# ESC.net
KiCad netlist of a schematic drawn in Altium Designer
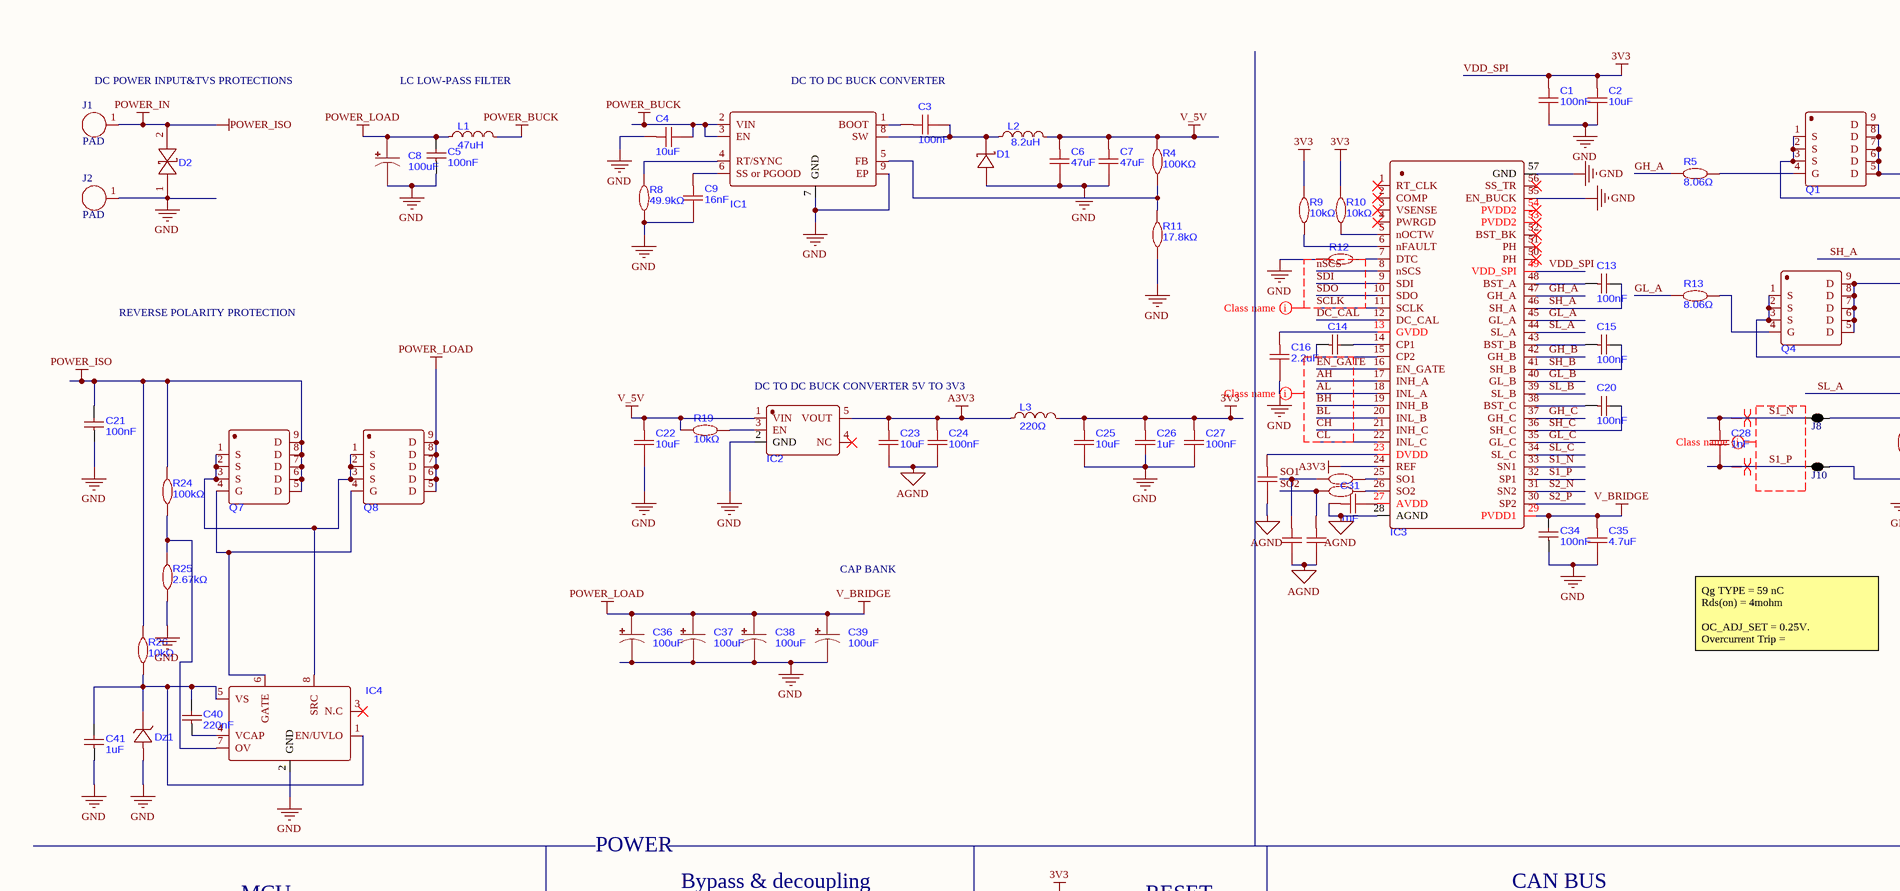
[diagram p0: ESC.SchDoc, top left]
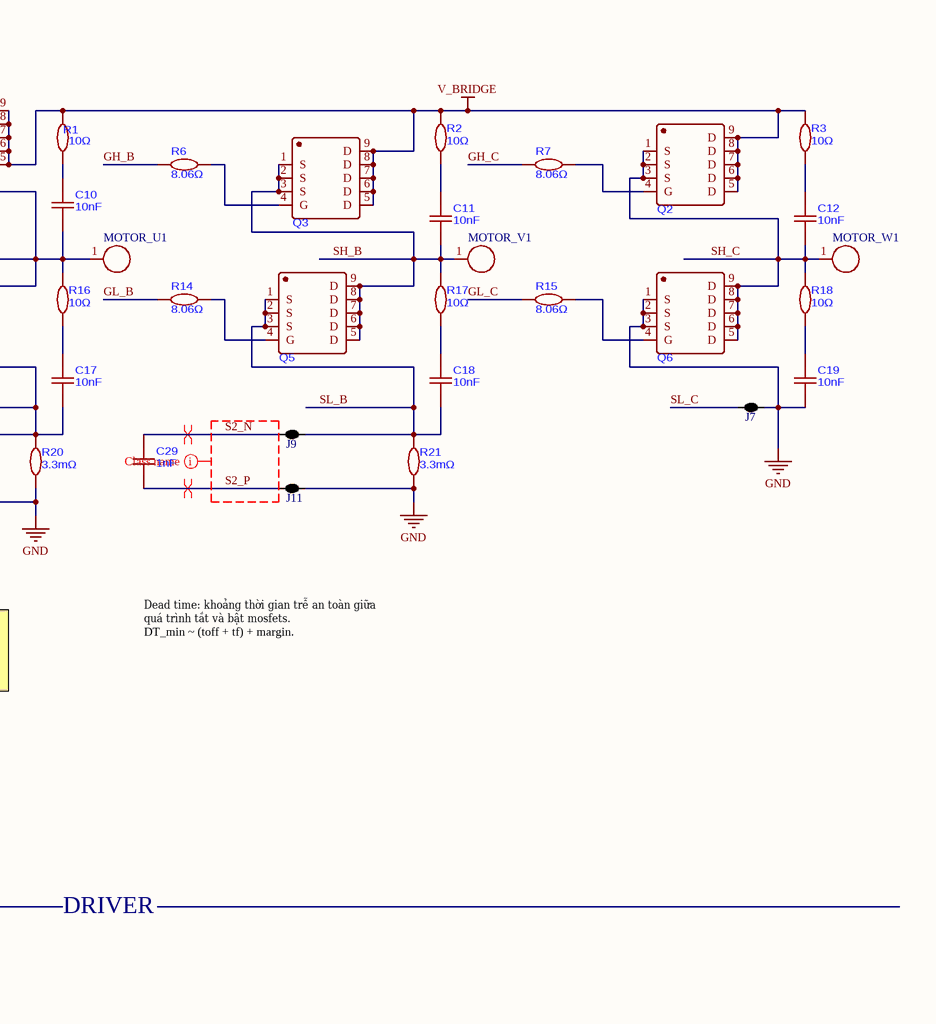
[diagram p1: ESC.SchDoc, top right]
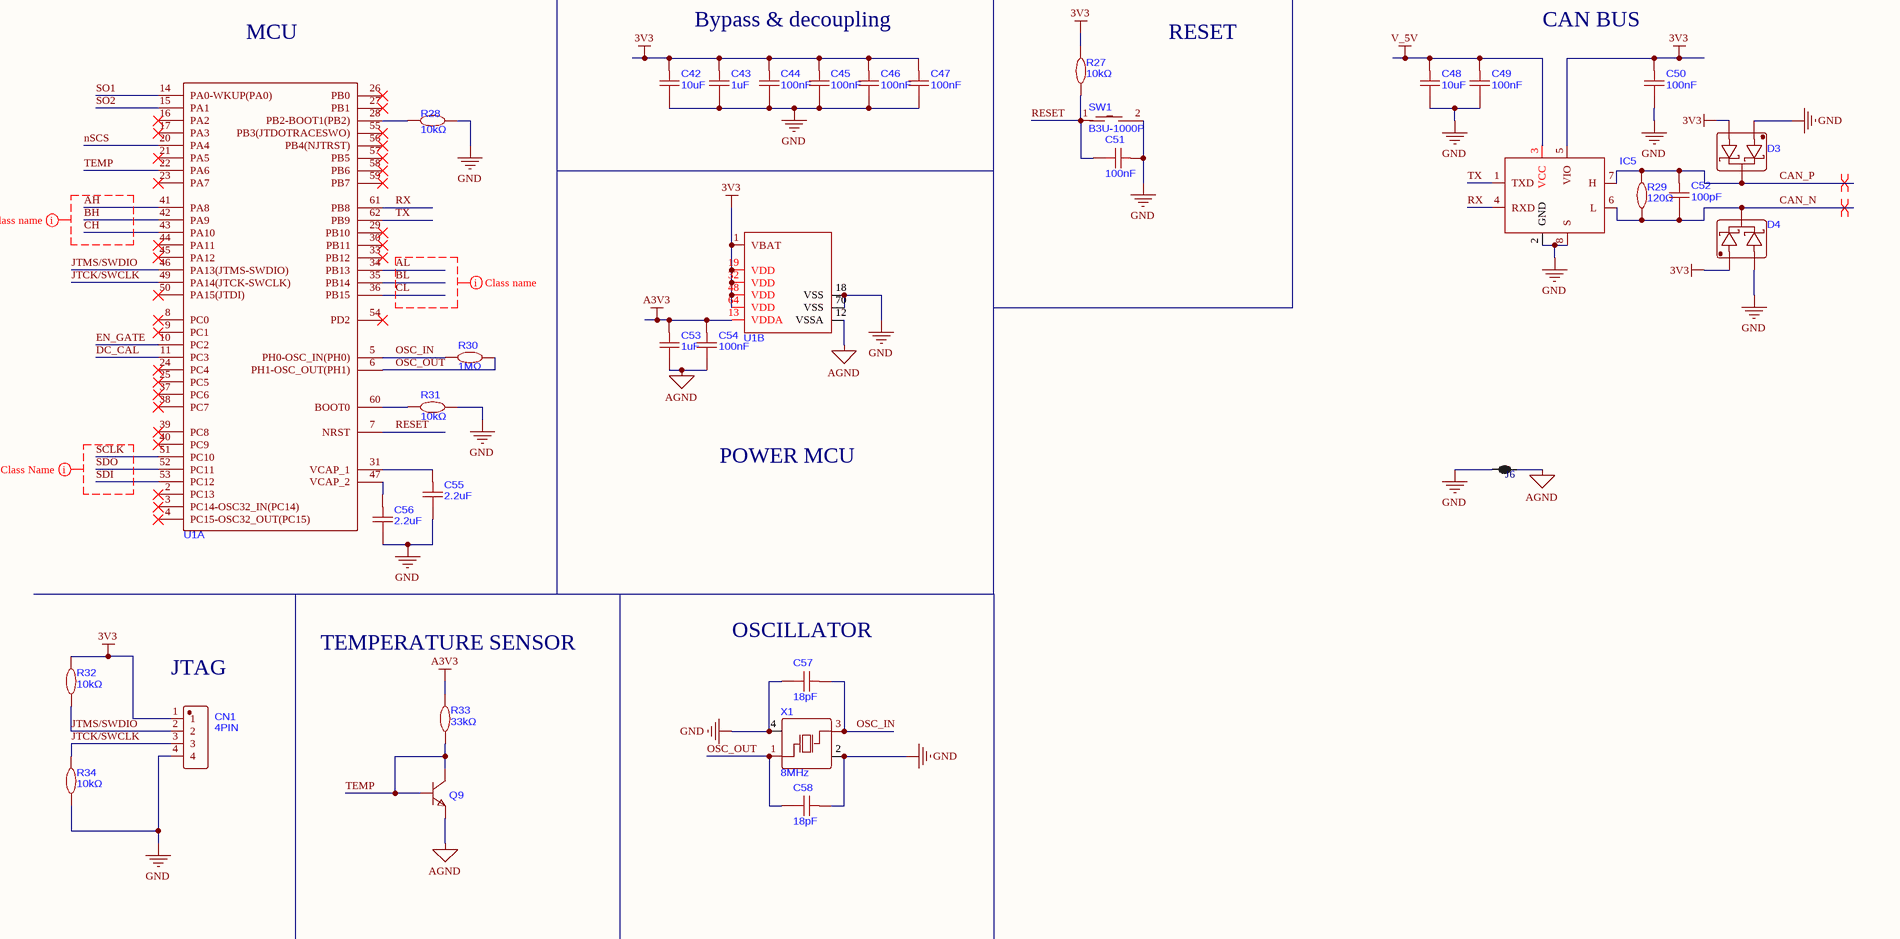
[diagram p2: ESC.SchDoc, bottom left]
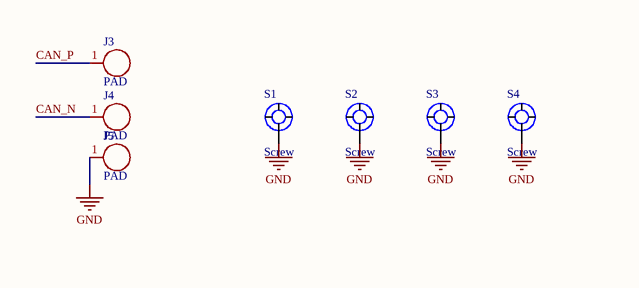
[diagram p3: ESC.SchDoc, bottom right]

(export (version "E")
  (design (tool "Eeschema 10.0.6"))
  (components
    (comp (ref "C1")
      (value "100nF")
      (footprint "C0603")
      (description "100nF ±10% 50V Ceramic Capacitor X7R 0603")
      (libsource (lib "ESC") (part "CC0603KRX7R9BB104"))
    )
    (comp (ref "C2")
      (value "10uF")
      (footprint "C0603")
      (description "10uF ±10% 10V Ceramic Capacitor X5R 0603")
      (libsource (lib "ESC") (part "CL10A106KP8NNNC"))
    )
    (comp (ref "C3")
      (value "100nF")
      (footprint "C0603")
      (description "100nF ±10% 50V Ceramic Capacitor X7R 0603")
      (libsource (lib "ESC") (part "CC0603KRX7R9BB104"))
    )
    (comp (ref "C4")
      (value "10uF")
      (footprint "C1206")
      (description "10uF X6S ±10% 100V 1206 Ceramic Capacitors RoHS")
      (libsource (lib "ESC") (part "C3216X6S2A106KT0A0E"))
    )
    (comp (ref "C5")
      (value "100nF")
      (footprint "C0805")
      (description "100nF ±10% 100V Ceramic Capacitor X7R 0805")
      (libsource (lib "ESC") (part "CL21B104KCFNNNE"))
    )
    (comp (ref "C6")
      (value "47uF")
      (footprint "C0603")
      (description "47uF ±20% 10V Ceramic Capacitor X5R 0805")
      (libsource (lib "ESC") (part "GRM21BR61A476ME15L_1"))
    )
    (comp (ref "C7")
      (value "47uF")
      (footprint "C0603")
      (description "47uF ±20% 10V Ceramic Capacitor X5R 0805")
      (libsource (lib "ESC") (part "GRM21BR61A476ME15L_1"))
    )
    (comp (ref "C8")
      (value "100uF")
      (footprint "CAP-SMD_BD10.0-L10.3-W10.3-FD")
      (description "100uF ±20% 100V Aluminum Electrolytic Capacitors")
      (libsource (lib "ESC") (part "EFVH100ADA101M10C0"))
    )
    (comp (ref "C9")
      (value "16nF")
      (footprint "C1206")
      (description "16nF ±5% 50V Ceramic Capacitor C0G 1206")
      (libsource (lib "ESC") (part "GRM3195C1H163JA01D"))
    )
    (comp (ref "C10")
      (value "10nF")
      (footprint "C0805")
      (description "10nF ±10% 100V Ceramic Capacitor X7R 0805")
      (libsource (lib "ESC") (part "CC0805KRX7R0BB103"))
    )
    (comp (ref "C11")
      (value "10nF")
      (footprint "C0805")
      (description "10nF ±10% 100V Ceramic Capacitor X7R 0805")
      (libsource (lib "ESC") (part "CC0805KRX7R0BB103"))
    )
    (comp (ref "C12")
      (value "10nF")
      (footprint "C0805")
      (description "10nF ±10% 100V Ceramic Capacitor X7R 0805")
      (libsource (lib "ESC") (part "CC0805KRX7R0BB103"))
    )
    (comp (ref "C13")
      (value "100nF")
      (footprint "C0805")
      (description "100nF ±10% 100V Ceramic Capacitor X7R 0805")
      (libsource (lib "ESC") (part "CL21B104KCFNNNE"))
    )
    (comp (ref "C14")
      (value "220nF")
      (footprint "C0805")
      (description "220nF ±10% 100V Ceramic Capacitor X7R 0805")
      (libsource (lib "ESC") (part "CC0805KKX7R0BB224"))
    )
    (comp (ref "C15")
      (value "100nF")
      (footprint "C0805")
      (description "100nF ±10% 100V Ceramic Capacitor X7R 0805")
      (libsource (lib "ESC") (part "CL21B104KCFNNNE"))
    )
    (comp (ref "C16")
      (value "2.2uF")
      (footprint "C0603")
      (description "2.2uF X5R ±10% 25V 0603 Ceramic Capacitors RoHS")
      (libsource (lib "ESC") (part "CC0603X5R25V225KN"))
    )
    (comp (ref "C17")
      (value "10nF")
      (footprint "C0805")
      (description "10nF ±10% 100V Ceramic Capacitor X7R 0805")
      (libsource (lib "ESC") (part "CC0805KRX7R0BB103"))
    )
    (comp (ref "C18")
      (value "10nF")
      (footprint "C0805")
      (description "10nF ±10% 100V Ceramic Capacitor X7R 0805")
      (libsource (lib "ESC") (part "CC0805KRX7R0BB103"))
    )
    (comp (ref "C19")
      (value "10nF")
      (footprint "C0805")
      (description "10nF ±10% 100V Ceramic Capacitor X7R 0805")
      (libsource (lib "ESC") (part "CC0805KRX7R0BB103"))
    )
    (comp (ref "C20")
      (value "100nF")
      (footprint "C0805")
      (description "100nF ±10% 100V Ceramic Capacitor X7R 0805")
      (libsource (lib "ESC") (part "CL21B104KCFNNNE"))
    )
    (comp (ref "C21")
      (value "100nF")
      (footprint "C0805")
      (description "100nF ±10% 100V Ceramic Capacitor X7R 0805")
      (libsource (lib "ESC") (part "CL21B104KCFNNNE"))
    )
    (comp (ref "C22")
      (value "10uF")
      (footprint "C0603")
      (description "10uF ±10% 10V Ceramic Capacitor X5R 0603")
      (libsource (lib "ESC") (part "CL10A106KP8NNNC"))
    )
    (comp (ref "C23")
      (value "10uF")
      (footprint "C0603")
      (description "10uF ±10% 10V Ceramic Capacitor X5R 0603")
      (libsource (lib "ESC") (part "CL10A106KP8NNNC"))
    )
    (comp (ref "C24")
      (value "100nF")
      (footprint "C0603")
      (description "100nF ±10% 50V Ceramic Capacitor X7R 0603")
      (libsource (lib "ESC") (part "CC0603KRX7R9BB104"))
    )
    (comp (ref "C25")
      (value "10uF")
      (footprint "C0603")
      (description "10uF ±10% 10V Ceramic Capacitor X5R 0603")
      (libsource (lib "ESC") (part "CL10A106KP8NNNC"))
    )
    (comp (ref "C26")
      (value "1uF")
      (footprint "C0603")
      (description "1uF ±10% 25V Ceramic Capacitor X7R 0603")
      (libsource (lib "ESC") (part "CL10B105KA8NNNC"))
    )
    (comp (ref "C27")
      (value "100nF")
      (footprint "C0603")
      (description "100nF ±10% 50V Ceramic Capacitor X7R 0603")
      (libsource (lib "ESC") (part "CC0603KRX7R9BB104"))
    )
    (comp (ref "C28")
      (value "1nF")
      (footprint "C0603")
      (description "1nF ±10% 50V Ceramic Capacitor X7R 0603")
      (libsource (lib "ESC") (part "CC0603KRX7R9BB102"))
    )
    (comp (ref "C29")
      (value "1nF")
      (footprint "C0603")
      (description "1nF ±10% 50V Ceramic Capacitor X7R 0603")
      (libsource (lib "ESC") (part "CC0603KRX7R9BB102"))
    )
    (comp (ref "C30")
      (value "1uF")
      (footprint "C0603")
      (description "1uF ±10% 25V Ceramic Capacitor X7R 0603")
      (libsource (lib "ESC") (part "CL10B105KA8NNNC"))
    )
    (comp (ref "C31")
      (value "1uF")
      (footprint "C0603")
      (description "1uF ±10% 25V Ceramic Capacitor X7R 0603")
      (libsource (lib "ESC") (part "CL10B105KA8NNNC"))
    )
    (comp (ref "C32")
      (value "2.2uF")
      (footprint "C0603")
      (description "2.2uF X5R ±10% 25V 0603 Ceramic Capacitors RoHS")
      (libsource (lib "ESC") (part "CC0603X5R25V225KN"))
    )
    (comp (ref "C33")
      (value "2.2uF")
      (footprint "C0603")
      (description "2.2uF X5R ±10% 25V 0603 Ceramic Capacitors RoHS")
      (libsource (lib "ESC") (part "CC0603X5R25V225KN"))
    )
    (comp (ref "C34")
      (value "100nF")
      (footprint "C0805")
      (description "100nF ±10% 100V Ceramic Capacitor X7R 0805")
      (libsource (lib "ESC") (part "CL21B104KCFNNNE"))
    )
    (comp (ref "C35")
      (value "4.7uF")
      (footprint "C0805")
      (description "4.7uF ±10% 100V Ceramic Capacitor X5R 0805")
      (libsource (lib "ESC") (part "CIA0805X5R475K101MT"))
    )
    (comp (ref "C36")
      (value "100uF")
      (footprint "CAP-SMD_BD10.0-L10.3-W10.3-FD")
      (description "100uF ±20% 100V Aluminum Electrolytic Capacitors")
      (libsource (lib "ESC") (part "EFVH100ADA101M10C0"))
    )
    (comp (ref "C37")
      (value "100uF")
      (footprint "CAP-SMD_BD10.0-L10.3-W10.3-FD")
      (description "100uF ±20% 100V Aluminum Electrolytic Capacitors")
      (libsource (lib "ESC") (part "EFVH100ADA101M10C0"))
    )
    (comp (ref "C38")
      (value "100uF")
      (footprint "CAP-SMD_BD10.0-L10.3-W10.3-FD")
      (description "100uF ±20% 100V Aluminum Electrolytic Capacitors")
      (libsource (lib "ESC") (part "EFVH100ADA101M10C0"))
    )
    (comp (ref "C39")
      (value "100uF")
      (footprint "CAP-SMD_BD10.0-L10.3-W10.3-FD")
      (description "100uF ±20% 100V Aluminum Electrolytic Capacitors")
      (libsource (lib "ESC") (part "EFVH100ADA101M10C0"))
    )
    (comp (ref "C40")
      (value "220nF")
      (footprint "C0603")
      (description "220nF ±10% 100V Ceramic Capacitor X7S 0603")
      (libsource (lib "ESC") (part "CGA0603X7S224K101JT"))
    )
    (comp (ref "C41")
      (value "1uF")
      (footprint "C0603")
      (description "1uF ±10% 100V Ceramic Capacitor X7T 0603")
      (libsource (lib "ESC") (part "GRM188D72A105KE01D"))
    )
    (comp (ref "C42")
      (value "10uF")
      (footprint "C0603")
      (description "10uF ±10% 10V Ceramic Capacitor X5R 0603")
      (libsource (lib "ESC") (part "CL10A106KP8NNNC"))
    )
    (comp (ref "C43")
      (value "1uF")
      (footprint "C0603")
      (description "1uF ±10% 25V Ceramic Capacitor X7R 0603")
      (libsource (lib "ESC") (part "CL10B105KA8NNNC"))
    )
    (comp (ref "C44")
      (value "100nF")
      (footprint "C0603")
      (description "100nF ±10% 50V Ceramic Capacitor X7R 0603")
      (libsource (lib "ESC") (part "CC0603KRX7R9BB104"))
    )
    (comp (ref "C45")
      (value "100nF")
      (footprint "C0603")
      (description "100nF ±10% 50V Ceramic Capacitor X7R 0603")
      (libsource (lib "ESC") (part "CC0603KRX7R9BB104"))
    )
    (comp (ref "C46")
      (value "100nF")
      (footprint "C0603")
      (description "100nF ±10% 50V Ceramic Capacitor X7R 0603")
      (libsource (lib "ESC") (part "CC0603KRX7R9BB104"))
    )
    (comp (ref "C47")
      (value "100nF")
      (footprint "C0603")
      (description "100nF ±10% 50V Ceramic Capacitor X7R 0603")
      (libsource (lib "ESC") (part "CC0603KRX7R9BB104"))
    )
    (comp (ref "C48")
      (value "10uF")
      (footprint "C0603")
      (description "10uF ±10% 10V Ceramic Capacitor X5R 0603")
      (libsource (lib "ESC") (part "CL10A106KP8NNNC"))
    )
    (comp (ref "C49")
      (value "100nF")
      (footprint "C0603")
      (description "100nF ±10% 50V Ceramic Capacitor X7R 0603")
      (libsource (lib "ESC") (part "CC0603KRX7R9BB104"))
    )
    (comp (ref "C50")
      (value "100nF")
      (footprint "C0603")
      (description "100nF ±10% 50V Ceramic Capacitor X7R 0603")
      (libsource (lib "ESC") (part "CC0603KRX7R9BB104"))
    )
    (comp (ref "C51")
      (value "100nF")
      (footprint "C0603")
      (description "100nF ±10% 50V Ceramic Capacitor X7R 0603")
      (libsource (lib "ESC") (part "CC0603KRX7R9BB104"))
    )
    (comp (ref "C52")
      (value "100pF")
      (footprint "C0603")
      (description "100pF ±5% 50V Ceramic Capacitor C0G 0603")
      (libsource (lib "ESC") (part "CL10C101JB8NNNC"))
    )
    (comp (ref "C53")
      (value "1uF")
      (footprint "C0603")
      (description "1uF ±10% 25V Ceramic Capacitor X7R 0603")
      (libsource (lib "ESC") (part "CL10B105KA8NNNC"))
    )
    (comp (ref "C54")
      (value "100nF")
      (footprint "C0603")
      (description "100nF ±10% 50V Ceramic Capacitor X7R 0603")
      (libsource (lib "ESC") (part "CC0603KRX7R9BB104"))
    )
    (comp (ref "C55")
      (value "2.2uF")
      (footprint "C0603")
      (description "2.2uF X5R ±10% 25V 0603 Ceramic Capacitors RoHS")
      (libsource (lib "ESC") (part "CC0603X5R25V225KN"))
    )
    (comp (ref "C56")
      (value "2.2uF")
      (footprint "C0603")
      (description "2.2uF X5R ±10% 25V 0603 Ceramic Capacitors RoHS")
      (libsource (lib "ESC") (part "CC0603X5R25V225KN"))
    )
    (comp (ref "C57")
      (value "18pF")
      (footprint "C0603")
      (description "18pF ±5% 50V Ceramic Capacitor C0G 0603")
      (libsource (lib "ESC") (part "CL10C180JB8NNNC"))
    )
    (comp (ref "C58")
      (value "18pF")
      (footprint "C0603")
      (description "18pF ±5% 50V Ceramic Capacitor C0G 0603")
      (libsource (lib "ESC") (part "CL10C180JB8NNNC"))
    )
    (comp (ref "CN1")
      (value "4PIN")
      (footprint "HDR-TH_4P-HX-PH254-01-04-Z-L11.5")
      (libsource (lib "ESC") (part "HX PH254-01-04-Z-L11.5 STRAIGHT PIN HEADER"))
    )
    (comp (ref "D1")
      (value "DIODE SCHOTTKY 100V DO-214AB")
      (footprint "SMC_L7.1-W6.2-LS8.1-RD")
      (description "Diode 100V 3A Surface Mount DO-214AB")
      (libsource (lib "ESC") (part "MBRS3100T3G"))
    )
    (comp (ref "D2")
      (value "93.6V 1.5kW@10/1000us Unidirectional 58V SMC TVS Diodes RoHS")
      (footprint "SMC_L6.9-W5.9-LS7.9-RD")
      (libsource (lib "ESC") (part "VISHAY SMCJ58A-E3/57T"))
    )
    (comp (ref "D3")
      (value "DIODE ARR SCHOTTKY 30V SOT-23")
      (footprint "SOT-23-3_L2.9-W1.3-P1.90-LS2.4-BR")
      (description "600mA 30V 1 Pair Common Cathode 1V@100mA 200mA SOT-23 Single Diodes RoHS")
      (libsource (lib "ESC") (part "BAT54C_C916424"))
    )
    (comp (ref "D4")
      (value "DIODE ARR SCHOTTKY 30V SOT-23")
      (footprint "SOT-23-3_L2.9-W1.3-P1.90-LS2.4-BR")
      (description "600mA 30V 1 Pair Common Cathode 1V@100mA 200mA SOT-23 Single Diodes RoHS")
      (libsource (lib "ESC") (part "BAT54C_C916424"))
    )
    (comp (ref "Dz1")
      (value "DIODE ZENER 56V 500mW SOD-123W")
      (footprint "SOD-123_L2.8-W1.8-LS3.7-RD")
      (description "Zener Diode Independent 56V 500mW Surface Mount SOD-123W")
      (libsource (lib "ESC") (part "BZT52C56"))
    )
    (comp (ref "IC1")
      (value "60V 3A Step-Down Converter")
      (footprint "SOIC-8_L4.9-W3.9-P1.27-LS6.0-BL-EP2.3")
      (libsource (lib "ESC") (part "LMR16030SDDAR"))
    )
    (comp (ref "IC2")
      (value "500mA Low-Noise LDo Voltage Regulator")
      (footprint "SOT-23-5_L2.9-W1.6-P0.95-LS2.8-BR")
      (description "3.3V 16V Positive Fixed SOT-23-5 Voltage Regulators - Linear, Low Drop Out (LDO) Regulators RoHS")
      (libsource (lib "ESC") (part "SPX3819M5-L-3-3"))
    )
    (comp (ref "IC3")
      (value "DRV8301 Three-Phase Gate Driver With Dual Current Shunt Amplifiers and Buck Regulator")
      (footprint "HTSSOP-56_L14.0-W6.0-P0.50-LS8.1-BL-EP")
      (description "MOSFET 1.7A 2.3A HTSSOP-56-EP-6mm Motor Drivers, Controllers RoHS")
      (libsource (lib "ESC") (part "DRV8301DCA"))
    )
    (comp (ref "IC4")
      (value "TSOT-23-8 OR Controllers, Ideal Diodes RoHS")
      (footprint "SOT-23-8_L2.9-W1.6-P0.65-LS2.8-BL")
      (libsource (lib "ESC") (part "LM74502DDFR"))
    )
    (comp (ref "IC5")
      (value "High-speed CAN transceiver")
      (footprint "SOIC-8_L4.9-W3.9-P1.27-LS6.0-BL")
      (description "4.5V~5.5V CAN FD Transceiver SOIC-8-150mil Drivers, Receivers, Transceivers RoHS")
      (libsource (lib "ESC") (part "TJA1051T/3/1J"))
    )
    (comp (ref "J1") (value "PAD") (footprint "PAD") (libsource (lib "ESC") (part "PAD")))
    (comp (ref "J2") (value "PAD") (footprint "PAD") (libsource (lib "ESC") (part "PAD")))
    (comp (ref "J3") (value "PAD") (footprint "PAD") (libsource (lib "ESC") (part "PAD")))
    (comp (ref "J4") (value "PAD") (footprint "PAD") (libsource (lib "ESC") (part "PAD")))
    (comp (ref "J5") (value "PAD") (footprint "PAD") (libsource (lib "ESC") (part "PAD")))
    (comp (ref "J6")
      (value "2 way net tie junction")
      (footprint "2way_HP")
      (libsource (lib "ESC") (part "2way"))
    )
    (comp (ref "J7")
      (value "2 way net tie junction")
      (footprint "2way_LP")
      (libsource (lib "ESC") (part "2way"))
    )
    (comp (ref "J8")
      (value "2 way net tie junction")
      (footprint "2way_LP")
      (libsource (lib "ESC") (part "2way"))
    )
    (comp (ref "J9")
      (value "2 way net tie junction")
      (footprint "2way_LP")
      (libsource (lib "ESC") (part "2way"))
    )
    (comp (ref "J10")
      (value "2 way net tie junction")
      (footprint "2way_LP")
      (libsource (lib "ESC") (part "2way"))
    )
    (comp (ref "J11")
      (value "2 way net tie junction")
      (footprint "2way_LP")
      (libsource (lib "ESC") (part "2way"))
    )
    (comp (ref "L1")
      (value "47uH")
      (footprint "IND-SMD_L12.3-W12.3")
      (description "2.5A 47uH 4.6A 100mΩ Magnetic Shielded Inductor ±20% SMD,12.3x12.3mm Fixed Inductors RoHS")
      (libsource (lib "ESC") (part "SMDRI127-470MT"))
    )
    (comp (ref "L2")
      (value "8.2uH")
      (footprint "IND-SMD_L7.0-W6.6_FXL0630")
      (description "5A 8.2uH 6A 60mΩ Molded Inductor ±20% SMD,7x6.6mm Fixed Inductors RoHS")
      (libsource (lib "ESC") (part "FXL0630-8R2-M"))
    )
    (comp (ref "L3")
      (value "220Ω")
      (footprint "C0805")
      (description "220Ω@100MHz 1 Line Ferrite Bead 0805 2A 45mΩ")
      (libsource (lib "ESC") (part "BLM21PG221SN1D"))
    )
    (comp (ref "MOTOR_U1") (value "PAD") (footprint "PAD") (libsource (lib "ESC") (part "PAD")))
    (comp (ref "MOTOR_V1") (value "PAD") (footprint "PAD") (libsource (lib "ESC") (part "PAD")))
    (comp (ref "MOTOR_W1") (value "PAD") (footprint "PAD") (libsource (lib "ESC") (part "PAD")))
    (comp (ref "Q1")
      (value "MOSFET N-CH 80V 100A SOP-8-Advance")
      (footprint "SOP-8_L5.0-W5.0-P1.27-LS6.0_TPH4R008NH-L1Q")
      (description "N-Channel 80V 100A 78W SOP-8-Advance")
      (libsource (lib "ESC") (part "TPH4R008NH,L1Q(M"))
    )
    (comp (ref "Q2")
      (value "MOSFET N-CH 80V 100A SOP-8-Advance")
      (footprint "SOP-8_L5.0-W5.0-P1.27-LS6.0_TPH4R008NH-L1Q")
      (description "N-Channel 80V 100A 78W SOP-8-Advance")
      (libsource (lib "ESC") (part "TPH4R008NH,L1Q(M"))
    )
    (comp (ref "Q3")
      (value "MOSFET N-CH 80V 100A SOP-8-Advance")
      (footprint "SOP-8_L5.0-W5.0-P1.27-LS6.0_TPH4R008NH-L1Q")
      (description "N-Channel 80V 100A 78W SOP-8-Advance")
      (libsource (lib "ESC") (part "TPH4R008NH,L1Q(M"))
    )
    (comp (ref "Q4")
      (value "MOSFET N-CH 80V 100A SOP-8-Advance")
      (footprint "SOP-8_L5.0-W5.0-P1.27-LS6.0_TPH4R008NH-L1Q")
      (description "N-Channel 80V 100A 78W SOP-8-Advance")
      (libsource (lib "ESC") (part "TPH4R008NH,L1Q(M"))
    )
    (comp (ref "Q5")
      (value "MOSFET N-CH 80V 100A SOP-8-Advance")
      (footprint "SOP-8_L5.0-W5.0-P1.27-LS6.0_TPH4R008NH-L1Q")
      (description "N-Channel 80V 100A 78W SOP-8-Advance")
      (libsource (lib "ESC") (part "TPH4R008NH,L1Q(M"))
    )
    (comp (ref "Q6")
      (value "MOSFET N-CH 80V 100A SOP-8-Advance")
      (footprint "SOP-8_L5.0-W5.0-P1.27-LS6.0_TPH4R008NH-L1Q")
      (description "N-Channel 80V 100A 78W SOP-8-Advance")
      (libsource (lib "ESC") (part "TPH4R008NH,L1Q(M"))
    )
    (comp (ref "Q7")
      (value "MOSFET N-CH 80V 100A SOP-8-Advance")
      (footprint "SOP-8_L5.0-W5.0-P1.27-LS6.0_TPH4R008NH-L1Q")
      (description "N-Channel 80V 100A 78W SOP-8-Advance")
      (libsource (lib "ESC") (part "TPH4R008NH,L1Q(M"))
    )
    (comp (ref "Q8")
      (value "MOSFET N-CH 80V 100A SOP-8-Advance")
      (footprint "SOP-8_L5.0-W5.0-P1.27-LS6.0_TPH4R008NH-L1Q")
      (description "N-Channel 80V 100A 78W SOP-8-Advance")
      (libsource (lib "ESC") (part "TPH4R008NH,L1Q(M"))
    )
    (comp (ref "Q9")
      (value "TRANS NPN 40V 200mA SOT-416")
      (footprint "SC-75-3_L1.6-W0.8-P1.00-LS1.6-BR")
      (description "Bipolar (BJT) Transistor NPN 40V 200mA 300MHz 200mW Surface Mount SOT-416")
      (libsource (lib "ESC") (part "MMBT3904TT1G"))
    )
    (comp (ref "R1")
      (value "10Ω")
      (footprint "R0805")
      (description "10Ω 500mW Thick Film Resistor ±100ppm/℃ ±1% 0805 Chip Resistor - Surface Mount RoHS")
      (libsource (lib "ESC") (part "CRCW080510R0FKEAHP"))
    )
    (comp (ref "R2")
      (value "10Ω")
      (footprint "R0805")
      (description "10Ω 500mW Thick Film Resistor ±100ppm/℃ ±1% 0805 Chip Resistor - Surface Mount RoHS")
      (libsource (lib "ESC") (part "CRCW080510R0FKEAHP"))
    )
    (comp (ref "R3")
      (value "10Ω")
      (footprint "R0805")
      (description "10Ω 500mW Thick Film Resistor ±100ppm/℃ ±1% 0805 Chip Resistor - Surface Mount RoHS")
      (libsource (lib "ESC") (part "CRCW080510R0FKEAHP"))
    )
    (comp (ref "R4")
      (value "100KΩ")
      (footprint "R0603")
      (description "100mW 100kΩ 75V Thick Film Resistor ±100ppm/℃ ±1% 0603 Chip Resistor - Surface Mount RoHS")
      (libsource (lib "ESC") (part "RC0603FR-07100KL"))
    )
    (comp (ref "R5")
      (value "8.06Ω")
      (footprint "R1206")
      (description "8.06Ω ±1% 250mW 1206 Thick Film Resistor")
      (libsource (lib "ESC") (part "FRC1206F8R06TS"))
    )
    (comp (ref "R6")
      (value "8.06Ω")
      (footprint "R1206")
      (description "8.06Ω ±1% 250mW 1206 Thick Film Resistor")
      (libsource (lib "ESC") (part "FRC1206F8R06TS"))
    )
    (comp (ref "R7")
      (value "8.06Ω")
      (footprint "R1206")
      (description "8.06Ω ±1% 250mW 1206 Thick Film Resistor")
      (libsource (lib "ESC") (part "FRC1206F8R06TS"))
    )
    (comp (ref "R8")
      (value "49.9kΩ")
      (footprint "R0603")
      (description "100mW 49.9kΩ 75V Thick Film Resistor ±100ppm/℃ ±1% 0603 Chip Resistor - Surface Mount RoHS")
      (libsource (lib "ESC") (part "RC0603FR-0749K9L"))
    )
    (comp (ref "R9")
      (value "10kΩ")
      (footprint "R0603")
      (description "100mW 10kΩ 75V ±100ppm/℃ Thick Film Resistor ±1% 0603 Chip Resistor - Surface Mount ROHS")
      (libsource (lib "ESC") (part "RC0603FR-0710KL"))
    )
    (comp (ref "R10")
      (value "10kΩ")
      (footprint "R0603")
      (description "100mW 10kΩ 75V ±100ppm/℃ Thick Film Resistor ±1% 0603 Chip Resistor - Surface Mount ROHS")
      (libsource (lib "ESC") (part "RC0603FR-0710KL"))
    )
    (comp (ref "R11")
      (value "17.8kΩ")
      (footprint "R0603")
      (description "17.8kΩ ±1% 100mW 0603 Thick Film Resistor")
      (libsource (lib "ESC") (part "0603WAF1782T5E"))
    )
    (comp (ref "R12")
      (value "24.9KΩ")
      (footprint "R0603")
      (description "24.9kΩ ±1% 100mW 0603 Thick Film Resistor")
      (libsource (lib "ESC") (part "FRC0603F2492TS"))
    )
    (comp (ref "R13")
      (value "8.06Ω")
      (footprint "R1206")
      (description "8.06Ω ±1% 250mW 1206 Thick Film Resistor")
      (libsource (lib "ESC") (part "FRC1206F8R06TS"))
    )
    (comp (ref "R14")
      (value "8.06Ω")
      (footprint "R1206")
      (description "8.06Ω ±1% 250mW 1206 Thick Film Resistor")
      (libsource (lib "ESC") (part "FRC1206F8R06TS"))
    )
    (comp (ref "R15")
      (value "8.06Ω")
      (footprint "R1206")
      (description "8.06Ω ±1% 250mW 1206 Thick Film Resistor")
      (libsource (lib "ESC") (part "FRC1206F8R06TS"))
    )
    (comp (ref "R16")
      (value "10Ω")
      (footprint "R0805")
      (description "10Ω 500mW Thick Film Resistor ±100ppm/℃ ±1% 0805 Chip Resistor - Surface Mount RoHS")
      (libsource (lib "ESC") (part "CRCW080510R0FKEAHP"))
    )
    (comp (ref "R17")
      (value "10Ω")
      (footprint "R0805")
      (description "10Ω 500mW Thick Film Resistor ±100ppm/℃ ±1% 0805 Chip Resistor - Surface Mount RoHS")
      (libsource (lib "ESC") (part "CRCW080510R0FKEAHP"))
    )
    (comp (ref "R18")
      (value "10Ω")
      (footprint "R0805")
      (description "10Ω 500mW Thick Film Resistor ±100ppm/℃ ±1% 0805 Chip Resistor - Surface Mount RoHS")
      (libsource (lib "ESC") (part "CRCW080510R0FKEAHP"))
    )
    (comp (ref "R19")
      (value "10kΩ")
      (footprint "R0603")
      (description "100mW 10kΩ 75V ±100ppm/℃ Thick Film Resistor ±1% 0603 Chip Resistor - Surface Mount ROHS")
      (libsource (lib "ESC") (part "RC0603FR-0710KL"))
    )
    (comp (ref "R20")
      (value "3.3mΩ")
      (footprint "R2512")
      (description "3.3mΩ 3W Current Sense Resistor ±1% ±150ppm/℃ 2512 Chip Resistor - Surface Mount RoHS")
      (libsource (lib "ESC") (part "WSLP25123L300FEA"))
    )
    (comp (ref "R21")
      (value "3.3mΩ")
      (footprint "R2512")
      (description "3.3mΩ 3W Current Sense Resistor ±1% ±150ppm/℃ 2512 Chip Resistor - Surface Mount RoHS")
      (libsource (lib "ESC") (part "WSLP25123L300FEA"))
    )
    (comp (ref "R22")
      (value "56Ω")
      (footprint "R0603")
      (description "56Ω ±1% 100mW 0603 Thick Film Resistor")
      (libsource (lib "ESC") (part "FRC0603F56R0TS"))
    )
    (comp (ref "R23")
      (value "56Ω")
      (footprint "R0603")
      (description "56Ω ±1% 100mW 0603 Thick Film Resistor")
      (libsource (lib "ESC") (part "FRC0603F56R0TS"))
    )
    (comp (ref "R24")
      (value "100kΩ")
      (footprint "R0603")
      (description "100mW 10kΩ 75V ±100ppm/℃ Thick Film Resistor ±1% 0603 Chip Resistor - Surface Mount ROHS")
      (libsource (lib "ESC") (part "RC0603FR-0710KL"))
    )
    (comp (ref "R25")
      (value "2.67kΩ")
      (footprint "R0603")
      (description "100mW 10kΩ 75V ±100ppm/℃ Thick Film Resistor ±1% 0603 Chip Resistor - Surface Mount ROHS")
      (libsource (lib "ESC") (part "RC0603FR-0710KL"))
    )
    (comp (ref "R26")
      (value "10kΩ")
      (footprint "R0603")
      (description "100mW 10kΩ 75V ±100ppm/℃ Thick Film Resistor ±1% 0603 Chip Resistor - Surface Mount ROHS")
      (libsource (lib "ESC") (part "RC0603FR-0710KL"))
    )
    (comp (ref "R27")
      (value "10kΩ")
      (footprint "R0603")
      (description "100mW 10kΩ 75V ±100ppm/℃ Thick Film Resistor ±1% 0603 Chip Resistor - Surface Mount ROHS")
      (libsource (lib "ESC") (part "RC0603FR-0710KL"))
    )
    (comp (ref "R28")
      (value "10kΩ")
      (footprint "R0603")
      (description "100mW 10kΩ 75V ±100ppm/℃ Thick Film Resistor ±1% 0603 Chip Resistor - Surface Mount ROHS")
      (libsource (lib "ESC") (part "RC0603FR-0710KL"))
    )
    (comp (ref "R29")
      (value "120Ω")
      (footprint "R0603")
      (description "120Ω ±1% 100mW 0603 Thick Film Resistor")
      (libsource (lib "ESC") (part "0603WAF1200T5E"))
    )
    (comp (ref "R30")
      (value "1MΩ")
      (footprint "R0603")
      (description "100mW 1MΩ 75V Thick Film Resistor ±100ppm/℃ ±1% 0603 Chip Resistor - Surface Mount RoHS")
      (libsource (lib "ESC") (part "RC0603FR-071ML"))
    )
    (comp (ref "R31")
      (value "10kΩ")
      (footprint "R0603")
      (description "100mW 10kΩ 75V ±100ppm/℃ Thick Film Resistor ±1% 0603 Chip Resistor - Surface Mount ROHS")
      (libsource (lib "ESC") (part "RC0603FR-0710KL"))
    )
    (comp (ref "R32")
      (value "10kΩ")
      (footprint "R0603")
      (description "100mW 10kΩ 75V ±100ppm/℃ Thick Film Resistor ±1% 0603 Chip Resistor - Surface Mount ROHS")
      (libsource (lib "ESC") (part "RC0603FR-0710KL"))
    )
    (comp (ref "R33")
      (value "33kΩ")
      (footprint "R0603")
      (description "100mW 33kΩ 75V Thick Film Resistor ±100ppm/℃ ±1% 0603 Chip Resistor - Surface Mount RoHS")
      (libsource (lib "ESC") (part "RC0603FR-0733KL"))
    )
    (comp (ref "R34")
      (value "10kΩ")
      (footprint "R0603")
      (description "100mW 10kΩ 75V ±100ppm/℃ Thick Film Resistor ±1% 0603 Chip Resistor - Surface Mount ROHS")
      (libsource (lib "ESC") (part "RC0603FR-0710KL"))
    )
    (comp (ref "S1") (value "Screw") (footprint "Screw Hole 4mm") (libsource (lib "ESC") (part "Screw")))
    (comp (ref "S2") (value "Screw") (footprint "Screw Hole 4mm") (libsource (lib "ESC") (part "Screw")))
    (comp (ref "S3") (value "Screw") (footprint "Screw Hole 4mm") (libsource (lib "ESC") (part "Screw")))
    (comp (ref "S4") (value "Screw") (footprint "Screw Hole 4mm") (libsource (lib "ESC") (part "Screw")))
    (comp (ref "SW1")
      (value "B3U-1000P")
      (footprint "KEY-SMD_B3U-1000PM")
      (description "12V 2.5mm Round Button 3mm SPST 50mA SMD,3x2.5mm Tactile Switches ROHS")
      (libsource (lib "ESC") (part "B3U-1000P"))
    )
    (comp (ref "U1")
      (value "ARM Cortex-M4 32b MCU+FPU, 210DMIPS, up to 1MB Flash/192+4KB RAM, USB OTG HS/FS, Ethernet, 17 TIMs, 3 ADCs, 15 comm. interfaces & camera")
      (footprint "LQFP-64_L10.0-W10.0-P0.50-LS12.0-BL")
      (description "ARM Cortex-M4 32 Bit 168MHz 51 LQFP-64(10x10) Microcontrollers RoHS")
      (libsource (lib "ESC") (part "STM32F405RGT6"))
    )
    (comp (ref "X1")
      (value "8MHz")
      (footprint "OSC-SMD_4P-L5.0-W3.2-BL")
      (description "Crystal 8MHz ±10ppm 10pF 200Ω SMD5032-4P")
      (libsource (lib "ESC") (part "ABM3B-8.000MHZ-10-1-U-T"))
    )
  )
  (nets
    (net (code "1") (name "/AH") (class "Default")
      (node (ref "IC3") (pin "17") (pinfunction "INH_A_17") (pintype "passive"))
      (node (ref "U1") (pin "41") (pinfunction "PA8_41") (pintype "passive"))
    )
    (net (code "2") (name "/AL") (class "Default")
      (node (ref "IC3") (pin "18") (pinfunction "INL_A_18") (pintype "passive"))
      (node (ref "U1") (pin "34") (pinfunction "PB13_34") (pintype "passive"))
    )
    (net (code "3") (name "/BH") (class "Default")
      (node (ref "IC3") (pin "19") (pinfunction "INH_B_19") (pintype "passive"))
      (node (ref "U1") (pin "42") (pinfunction "PA9_42") (pintype "passive"))
    )
    (net (code "4") (name "/BL") (class "Default")
      (node (ref "IC3") (pin "20") (pinfunction "INL_B_20") (pintype "passive"))
      (node (ref "U1") (pin "35") (pinfunction "PB14_35") (pintype "passive"))
    )
    (net (code "5") (name "/CAN_N") (class "Default")
      (node (ref "C52") (pin "1") (pinfunction "1_1") (pintype "passive"))
      (node (ref "D4") (pin "3") (pinfunction "3_3") (pintype "passive"))
      (node (ref "IC5") (pin "6") (pinfunction "L_6") (pintype "passive"))
      (node (ref "J4") (pin "1") (pintype "passive"))
      (node (ref "R29") (pin "1") (pinfunction "1_1") (pintype "passive"))
    )
    (net (code "6") (name "/CAN_P") (class "Default")
      (node (ref "C52") (pin "2") (pinfunction "2_2") (pintype "passive"))
      (node (ref "D3") (pin "3") (pinfunction "3_3") (pintype "passive"))
      (node (ref "IC5") (pin "7") (pinfunction "H_7") (pintype "passive"))
      (node (ref "J3") (pin "1") (pintype "passive"))
      (node (ref "R29") (pin "2") (pinfunction "2_2") (pintype "passive"))
    )
    (net (code "7") (name "/CH") (class "Default")
      (node (ref "IC3") (pin "21") (pinfunction "INH_C_21") (pintype "passive"))
      (node (ref "U1") (pin "43") (pinfunction "PA10_43") (pintype "passive"))
    )
    (net (code "8") (name "/CL") (class "Default")
      (node (ref "IC3") (pin "22") (pinfunction "INL_C_22") (pintype "passive"))
      (node (ref "U1") (pin "36") (pinfunction "PB15_36") (pintype "passive"))
    )
    (net (code "9") (name "/DC_CAL") (class "Default")
      (node (ref "IC3") (pin "12") (pinfunction "DC_CAL_12") (pintype "passive"))
      (node (ref "U1") (pin "11") (pinfunction "PC3_11") (pintype "passive"))
    )
    (net (code "10") (name "/EN_GATE") (class "Default")
      (node (ref "IC3") (pin "16") (pinfunction "EN_GATE_16") (pintype "passive"))
      (node (ref "U1") (pin "10") (pinfunction "PC2_10") (pintype "passive"))
    )
    (net (code "11") (name "/GH_A") (class "Default")
      (node (ref "IC3") (pin "47") (pinfunction "GH_A_47") (pintype "passive"))
      (node (ref "R5") (pin "1") (pinfunction "1_1") (pintype "passive"))
    )
    (net (code "12") (name "/GH_B") (class "Default")
      (node (ref "IC3") (pin "42") (pinfunction "GH_B_42") (pintype "passive"))
      (node (ref "R6") (pin "1") (pinfunction "1_1") (pintype "passive"))
    )
    (net (code "13") (name "/GH_C") (class "Default")
      (node (ref "IC3") (pin "37") (pinfunction "GH_C_37") (pintype "passive"))
      (node (ref "R7") (pin "1") (pinfunction "1_1") (pintype "passive"))
    )
    (net (code "14") (name "/GL_A") (class "Default")
      (node (ref "IC3") (pin "45") (pinfunction "GL_A_45") (pintype "passive"))
      (node (ref "R13") (pin "1") (pinfunction "1_1") (pintype "passive"))
    )
    (net (code "15") (name "/GL_B") (class "Default")
      (node (ref "IC3") (pin "40") (pinfunction "GL_B_40") (pintype "passive"))
      (node (ref "R14") (pin "1") (pinfunction "1_1") (pintype "passive"))
    )
    (net (code "16") (name "/GL_C") (class "Default")
      (node (ref "IC3") (pin "35") (pinfunction "GL_C_35") (pintype "passive"))
      (node (ref "R15") (pin "1") (pinfunction "1_1") (pintype "passive"))
    )
    (net (code "17") (name "/JTCK{slash}SWCLK") (class "Default")
      (node (ref "CN1") (pin "3") (pinfunction "3_3") (pintype "passive"))
      (node (ref "R34") (pin "2") (pinfunction "2_2") (pintype "passive"))
      (node (ref "U1") (pin "49") (pinfunction "PA14(JTCK-SWCLK)_49") (pintype "passive"))
    )
    (net (code "18") (name "/JTMS{slash}SWDIO") (class "Default")
      (node (ref "CN1") (pin "2") (pinfunction "2_2") (pintype "passive"))
      (node (ref "R32") (pin "1") (pinfunction "1_1") (pintype "passive"))
      (node (ref "U1") (pin "46") (pinfunction "PA13(JTMS-SWDIO)_46") (pintype "passive"))
    )
    (net (code "19") (name "/OSC_IN") (class "Default")
      (node (ref "C57") (pin "2") (pinfunction "2_2") (pintype "passive"))
      (node (ref "R30") (pin "2") (pinfunction "2_2") (pintype "passive"))
      (node (ref "U1") (pin "5") (pinfunction "PH0-OSC_IN(PH0)_5") (pintype "passive"))
      (node (ref "X1") (pin "3") (pinfunction "OSC2_3") (pintype "passive"))
    )
    (net (code "20") (name "/OSC_OUT") (class "Default")
      (node (ref "C58") (pin "1") (pinfunction "1_1") (pintype "passive"))
      (node (ref "R30") (pin "1") (pinfunction "1_1") (pintype "passive"))
      (node (ref "U1") (pin "6") (pinfunction "PH1-OSC_OUT(PH1)_6") (pintype "passive"))
      (node (ref "X1") (pin "1") (pinfunction "OSC1_1") (pintype "passive"))
    )
    (net (code "21") (name "/RESET") (class "Default")
      (node (ref "C51") (pin "1") (pinfunction "1_1") (pintype "passive"))
      (node (ref "R27") (pin "1") (pinfunction "1_1") (pintype "passive"))
      (node (ref "SW1") (pin "1") (pinfunction "1_1") (pintype "passive"))
      (node (ref "U1") (pin "7") (pinfunction "NRST_7") (pintype "passive"))
    )
    (net (code "22") (name "/RX") (class "Default")
      (node (ref "IC5") (pin "4") (pinfunction "RXD_4") (pintype "passive"))
      (node (ref "U1") (pin "61") (pinfunction "PB8_61") (pintype "passive"))
    )
    (net (code "23") (name "/S1_N") (class "Default")
      (node (ref "C28") (pin "2") (pinfunction "2_2") (pintype "passive"))
      (node (ref "IC3") (pin "33") (pinfunction "SN1_33") (pintype "passive"))
      (node (ref "J8") (pin "1") (pinfunction "1_1") (pintype "passive"))
    )
    (net (code "24") (name "/S1_P") (class "Default")
      (node (ref "C28") (pin "1") (pinfunction "1_1") (pintype "passive"))
      (node (ref "IC3") (pin "32") (pinfunction "SP1_32") (pintype "passive"))
      (node (ref "J10") (pin "1") (pinfunction "1_1") (pintype "passive"))
    )
    (net (code "25") (name "/S2_N") (class "Default")
      (node (ref "C29") (pin "2") (pinfunction "2_2") (pintype "passive"))
      (node (ref "IC3") (pin "31") (pinfunction "SN2_31") (pintype "passive"))
      (node (ref "J9") (pin "1") (pinfunction "1_1") (pintype "passive"))
    )
    (net (code "26") (name "/S2_P") (class "Default")
      (node (ref "C29") (pin "1") (pinfunction "1_1") (pintype "passive"))
      (node (ref "IC3") (pin "30") (pinfunction "SP2_30") (pintype "passive"))
      (node (ref "J11") (pin "1") (pinfunction "1_1") (pintype "passive"))
    )
    (net (code "27") (name "/SCLK") (class "Default")
      (node (ref "IC3") (pin "11") (pinfunction "SCLK_11") (pintype "passive"))
      (node (ref "U1") (pin "51") (pinfunction "PC10_51") (pintype "passive"))
    )
    (net (code "28") (name "/SDI") (class "Default")
      (node (ref "IC3") (pin "9") (pinfunction "SDI_9") (pintype "passive"))
      (node (ref "U1") (pin "53") (pinfunction "PC12_53") (pintype "passive"))
    )
    (net (code "29") (name "/SDO") (class "Default")
      (node (ref "IC3") (pin "10") (pinfunction "SDO_10") (pintype "passive"))
      (node (ref "U1") (pin "52") (pinfunction "PC11_52") (pintype "passive"))
    )
    (net (code "30") (name "/SH_A") (class "Default")
      (node (ref "C10") (pin "1") (pinfunction "1_1") (pintype "passive"))
      (node (ref "C13") (pin "2") (pinfunction "2_2") (pintype "passive"))
      (node (ref "IC3") (pin "46") (pinfunction "SH_A_46") (pintype "passive"))
      (node (ref "MOTOR_U1") (pin "1") (pintype "passive"))
      (node (ref "Q1") (pin "1") (pinfunction "S_1") (pintype "passive"))
      (node (ref "Q1") (pin "2") (pinfunction "S_2") (pintype "passive"))
      (node (ref "Q1") (pin "3") (pinfunction "S_3") (pintype "passive"))
      (node (ref "Q4") (pin "5") (pinfunction "D_5") (pintype "passive"))
      (node (ref "Q4") (pin "6") (pinfunction "D_6") (pintype "passive"))
      (node (ref "Q4") (pin "7") (pinfunction "D_7") (pintype "passive"))
      (node (ref "Q4") (pin "8") (pinfunction "D_8") (pintype "passive"))
      (node (ref "Q4") (pin "9") (pinfunction "D_9") (pintype "passive"))
      (node (ref "R16") (pin "2") (pinfunction "2_2") (pintype "passive"))
    )
    (net (code "31") (name "/SH_B") (class "Default")
      (node (ref "C11") (pin "1") (pinfunction "1_1") (pintype "passive"))
      (node (ref "C15") (pin "2") (pinfunction "2_2") (pintype "passive"))
      (node (ref "IC3") (pin "41") (pinfunction "SH_B_41") (pintype "passive"))
      (node (ref "MOTOR_V1") (pin "1") (pintype "passive"))
      (node (ref "Q3") (pin "1") (pinfunction "S_1") (pintype "passive"))
      (node (ref "Q3") (pin "2") (pinfunction "S_2") (pintype "passive"))
      (node (ref "Q3") (pin "3") (pinfunction "S_3") (pintype "passive"))
      (node (ref "Q5") (pin "5") (pinfunction "D_5") (pintype "passive"))
      (node (ref "Q5") (pin "6") (pinfunction "D_6") (pintype "passive"))
      (node (ref "Q5") (pin "7") (pinfunction "D_7") (pintype "passive"))
      (node (ref "Q5") (pin "8") (pinfunction "D_8") (pintype "passive"))
      (node (ref "Q5") (pin "9") (pinfunction "D_9") (pintype "passive"))
      (node (ref "R17") (pin "2") (pinfunction "2_2") (pintype "passive"))
    )
    (net (code "32") (name "/SH_C") (class "Default")
      (node (ref "C12") (pin "1") (pinfunction "1_1") (pintype "passive"))
      (node (ref "C20") (pin "2") (pinfunction "2_2") (pintype "passive"))
      (node (ref "IC3") (pin "36") (pinfunction "SH_C_36") (pintype "passive"))
      (node (ref "MOTOR_W1") (pin "1") (pintype "passive"))
      (node (ref "Q2") (pin "1") (pinfunction "S_1") (pintype "passive"))
      (node (ref "Q2") (pin "2") (pinfunction "S_2") (pintype "passive"))
      (node (ref "Q2") (pin "3") (pinfunction "S_3") (pintype "passive"))
      (node (ref "Q6") (pin "5") (pinfunction "D_5") (pintype "passive"))
      (node (ref "Q6") (pin "6") (pinfunction "D_6") (pintype "passive"))
      (node (ref "Q6") (pin "7") (pinfunction "D_7") (pintype "passive"))
      (node (ref "Q6") (pin "8") (pinfunction "D_8") (pintype "passive"))
      (node (ref "Q6") (pin "9") (pinfunction "D_9") (pintype "passive"))
      (node (ref "R18") (pin "2") (pinfunction "2_2") (pintype "passive"))
    )
    (net (code "33") (name "/SL_A") (class "Default")
      (node (ref "C17") (pin "1") (pinfunction "1_1") (pintype "passive"))
      (node (ref "IC3") (pin "44") (pinfunction "SL_A_44") (pintype "passive"))
      (node (ref "J8") (pin "2") (pinfunction "2_2") (pintype "passive"))
      (node (ref "Q4") (pin "1") (pinfunction "S_1") (pintype "passive"))
      (node (ref "Q4") (pin "2") (pinfunction "S_2") (pintype "passive"))
      (node (ref "Q4") (pin "3") (pinfunction "S_3") (pintype "passive"))
      (node (ref "R20") (pin "2") (pinfunction "2_2") (pintype "passive"))
    )
    (net (code "34") (name "/SL_B") (class "Default")
      (node (ref "C18") (pin "1") (pinfunction "1_1") (pintype "passive"))
      (node (ref "IC3") (pin "39") (pinfunction "SL_B_39") (pintype "passive"))
      (node (ref "J9") (pin "2") (pinfunction "2_2") (pintype "passive"))
      (node (ref "Q5") (pin "1") (pinfunction "S_1") (pintype "passive"))
      (node (ref "Q5") (pin "2") (pinfunction "S_2") (pintype "passive"))
      (node (ref "Q5") (pin "3") (pinfunction "S_3") (pintype "passive"))
      (node (ref "R21") (pin "2") (pinfunction "2_2") (pintype "passive"))
    )
    (net (code "35") (name "/SL_C") (class "Default")
      (node (ref "IC3") (pin "34") (pinfunction "SL_C_34") (pintype "passive"))
      (node (ref "J7") (pin "1") (pinfunction "1_1") (pintype "passive"))
    )
    (net (code "36") (name "/SO1") (class "Default")
      (node (ref "C32") (pin "2") (pinfunction "2_2") (pintype "passive"))
      (node (ref "R22") (pin "2") (pinfunction "2_2") (pintype "passive"))
      (node (ref "U1") (pin "14") (pinfunction "PA0-WKUP(PA0)_14") (pintype "passive"))
    )
    (net (code "37") (name "/SO2") (class "Default")
      (node (ref "C33") (pin "2") (pinfunction "2_2") (pintype "passive"))
      (node (ref "R23") (pin "2") (pinfunction "2_2") (pintype "passive"))
      (node (ref "U1") (pin "15") (pinfunction "PA1_15") (pintype "passive"))
    )
    (net (code "38") (name "/TEMP") (class "Default")
      (node (ref "Q9") (pin "1") (pinfunction "B_1") (pintype "passive"))
      (node (ref "Q9") (pin "3") (pinfunction "C_3") (pintype "passive"))
      (node (ref "R33") (pin "1") (pinfunction "1_1") (pintype "passive"))
      (node (ref "U1") (pin "22") (pinfunction "PA6_22") (pintype "passive"))
    )
    (net (code "39") (name "/TX") (class "Default")
      (node (ref "IC5") (pin "1") (pinfunction "TXD_1") (pintype "passive"))
      (node (ref "U1") (pin "62") (pinfunction "PB9_62") (pintype "passive"))
    )
    (net (code "40") (name "/nSCS") (class "Default")
      (node (ref "IC3") (pin "8") (pinfunction "nSCS_8") (pintype "passive"))
      (node (ref "U1") (pin "20") (pinfunction "PA4_20") (pintype "passive"))
    )
    (net (code "41") (name "3V3") (class "Default")
      (node (ref "C1") (pin "2") (pinfunction "2_2") (pintype "passive"))
      (node (ref "C2") (pin "2") (pinfunction "2_2") (pintype "passive"))
      (node (ref "C25") (pin "2") (pinfunction "2_2") (pintype "passive"))
      (node (ref "C26") (pin "2") (pinfunction "2_2") (pintype "passive"))
      (node (ref "C27") (pin "2") (pinfunction "2_2") (pintype "passive"))
      (node (ref "C42") (pin "2") (pinfunction "2_2") (pintype "passive"))
      (node (ref "C43") (pin "2") (pinfunction "2_2") (pintype "passive"))
      (node (ref "C44") (pin "2") (pinfunction "2_2") (pintype "passive"))
      (node (ref "C45") (pin "2") (pinfunction "2_2") (pintype "passive"))
      (node (ref "C46") (pin "2") (pinfunction "2_2") (pintype "passive"))
      (node (ref "C47") (pin "2") (pinfunction "2_2") (pintype "passive"))
      (node (ref "C50") (pin "2") (pinfunction "2_2") (pintype "passive"))
      (node (ref "CN1") (pin "1") (pinfunction "1_1") (pintype "passive"))
      (node (ref "D3") (pin "2") (pinfunction "2_2") (pintype "passive"))
      (node (ref "D4") (pin "1") (pinfunction "1_1") (pintype "passive"))
      (node (ref "IC3") (pin "49") (pinfunction "VDD_SPI_49") (pintype "passive"))
      (node (ref "IC5") (pin "5") (pinfunction "VIO_5") (pintype "passive"))
      (node (ref "L3") (pin "2") (pinfunction "2_2") (pintype "passive"))
      (node (ref "R10") (pin "1") (pinfunction "1_1") (pintype "passive"))
      (node (ref "R27") (pin "2") (pinfunction "2_2") (pintype "passive"))
      (node (ref "R32") (pin "2") (pinfunction "2_2") (pintype "passive"))
      (node (ref "R9") (pin "2") (pinfunction "2_2") (pintype "passive"))
      (node (ref "U1") (pin "1") (pinfunction "VBAT_1") (pintype "passive"))
      (node (ref "U1") (pin "19") (pinfunction "VDD_19") (pintype "passive"))
      (node (ref "U1") (pin "32") (pinfunction "VDD_32") (pintype "passive"))
      (node (ref "U1") (pin "48") (pinfunction "VDD_48") (pintype "passive"))
      (node (ref "U1") (pin "64") (pinfunction "VDD_64") (pintype "passive"))
    )
    (net (code "42") (name "A3V3") (class "Default")
      (node (ref "C23") (pin "2") (pinfunction "2_2") (pintype "passive"))
      (node (ref "C24") (pin "2") (pinfunction "2_2") (pintype "passive"))
      (node (ref "C53") (pin "2") (pinfunction "2_2") (pintype "passive"))
      (node (ref "C54") (pin "2") (pinfunction "2_2") (pintype "passive"))
      (node (ref "IC2") (pin "5") (pinfunction "VOUT_5") (pintype "passive"))
      (node (ref "IC3") (pin "24") (pinfunction "REF_24") (pintype "passive"))
      (node (ref "L3") (pin "1") (pinfunction "1_1") (pintype "passive"))
      (node (ref "R33") (pin "2") (pinfunction "2_2") (pintype "passive"))
      (node (ref "U1") (pin "13") (pinfunction "VDDA_13") (pintype "passive"))
    )
    (net (code "43") (name "AGND") (class "Default")
      (node (ref "C23") (pin "1") (pinfunction "1_1") (pintype "passive"))
      (node (ref "C24") (pin "1") (pinfunction "1_1") (pintype "passive"))
      (node (ref "C30") (pin "1") (pinfunction "1_1") (pintype "passive"))
      (node (ref "C31") (pin "2") (pinfunction "2_2") (pintype "passive"))
      (node (ref "C32") (pin "1") (pinfunction "1_1") (pintype "passive"))
      (node (ref "C33") (pin "1") (pinfunction "1_1") (pintype "passive"))
      (node (ref "C53") (pin "1") (pinfunction "1_1") (pintype "passive"))
      (node (ref "C54") (pin "1") (pinfunction "1_1") (pintype "passive"))
      (node (ref "IC3") (pin "28") (pinfunction "AGND_28") (pintype "passive"))
      (node (ref "J6") (pin "2") (pinfunction "2_2") (pintype "passive"))
      (node (ref "Q9") (pin "2") (pinfunction "E_2") (pintype "passive"))
      (node (ref "U1") (pin "12") (pinfunction "VSSA_12") (pintype "passive"))
    )
    (net (code "44") (name "GND") (class "Default")
      (node (ref "C1") (pin "1") (pinfunction "1_1") (pintype "passive"))
      (node (ref "C16") (pin "1") (pinfunction "1_1") (pintype "passive"))
      (node (ref "C19") (pin "1") (pinfunction "1_1") (pintype "passive"))
      (node (ref "C2") (pin "1") (pinfunction "1_1") (pintype "passive"))
      (node (ref "C21") (pin "1") (pinfunction "1_1") (pintype "passive"))
      (node (ref "C22") (pin "1") (pinfunction "1_1") (pintype "passive"))
      (node (ref "C25") (pin "1") (pinfunction "1_1") (pintype "passive"))
      (node (ref "C26") (pin "1") (pinfunction "1_1") (pintype "passive"))
      (node (ref "C27") (pin "1") (pinfunction "1_1") (pintype "passive"))
      (node (ref "C34") (pin "1") (pinfunction "1_1") (pintype "passive"))
      (node (ref "C35") (pin "1") (pinfunction "1_1") (pintype "passive"))
      (node (ref "C36") (pin "2") (pinfunction "2_2") (pintype "passive"))
      (node (ref "C37") (pin "2") (pinfunction "2_2") (pintype "passive"))
      (node (ref "C38") (pin "2") (pinfunction "2_2") (pintype "passive"))
      (node (ref "C39") (pin "2") (pinfunction "2_2") (pintype "passive"))
      (node (ref "C4") (pin "2") (pinfunction "2_2") (pintype "passive"))
      (node (ref "C41") (pin "1") (pinfunction "1_1") (pintype "passive"))
      (node (ref "C42") (pin "1") (pinfunction "1_1") (pintype "passive"))
      (node (ref "C43") (pin "1") (pinfunction "1_1") (pintype "passive"))
      (node (ref "C44") (pin "1") (pinfunction "1_1") (pintype "passive"))
      (node (ref "C45") (pin "1") (pinfunction "1_1") (pintype "passive"))
      (node (ref "C46") (pin "1") (pinfunction "1_1") (pintype "passive"))
      (node (ref "C47") (pin "1") (pinfunction "1_1") (pintype "passive"))
      (node (ref "C48") (pin "1") (pinfunction "1_1") (pintype "passive"))
      (node (ref "C49") (pin "1") (pinfunction "1_1") (pintype "passive"))
      (node (ref "C5") (pin "1") (pinfunction "1_1") (pintype "passive"))
      (node (ref "C50") (pin "1") (pinfunction "1_1") (pintype "passive"))
      (node (ref "C51") (pin "2") (pinfunction "2_2") (pintype "passive"))
      (node (ref "C55") (pin "1") (pinfunction "1_1") (pintype "passive"))
      (node (ref "C56") (pin "1") (pinfunction "1_1") (pintype "passive"))
      (node (ref "C57") (pin "1") (pinfunction "1_1") (pintype "passive"))
      (node (ref "C58") (pin "2") (pinfunction "2_2") (pintype "passive"))
      (node (ref "C6") (pin "1") (pinfunction "1_1") (pintype "passive"))
      (node (ref "C7") (pin "1") (pinfunction "1_1") (pintype "passive"))
      (node (ref "C8") (pin "2") (pinfunction "2_2") (pintype "passive"))
      (node (ref "C9") (pin "1") (pinfunction "1_1") (pintype "passive"))
      (node (ref "CN1") (pin "4") (pinfunction "4_4") (pintype "passive"))
      (node (ref "D1") (pin "2") (pinfunction "A_2") (pintype "passive"))
      (node (ref "D2") (pin "1") (pinfunction "1_1") (pintype "passive"))
      (node (ref "D3") (pin "1") (pinfunction "1_1") (pintype "passive"))
      (node (ref "D4") (pin "2") (pinfunction "2_2") (pintype "passive"))
      (node (ref "Dz1") (pin "2") (pinfunction "A_2") (pintype "passive"))
      (node (ref "IC1") (pin "7") (pinfunction "GND_7") (pintype "passive"))
      (node (ref "IC1") (pin "9") (pinfunction "EP_9") (pintype "passive"))
      (node (ref "IC2") (pin "2") (pinfunction "GND_2") (pintype "passive"))
      (node (ref "IC3") (pin "55") (pinfunction "EN_BUCK_55") (pintype "passive"))
      (node (ref "IC3") (pin "57") (pinfunction "GND_57") (pintype "passive"))
      (node (ref "IC4") (pin "2") (pinfunction "GND_2") (pintype "passive"))
      (node (ref "IC5") (pin "2") (pinfunction "GND_2") (pintype "passive"))
      (node (ref "IC5") (pin "8") (pinfunction "S_8") (pintype "passive"))
      (node (ref "J10") (pin "2") (pinfunction "2_2") (pintype "passive"))
      (node (ref "J11") (pin "2") (pinfunction "2_2") (pintype "passive"))
      (node (ref "J2") (pin "1") (pintype "passive"))
      (node (ref "J5") (pin "1") (pintype "passive"))
      (node (ref "J6") (pin "1") (pinfunction "1_1") (pintype "passive"))
      (node (ref "J7") (pin "2") (pinfunction "2_2") (pintype "passive"))
      (node (ref "Q6") (pin "1") (pinfunction "S_1") (pintype "passive"))
      (node (ref "Q6") (pin "2") (pinfunction "S_2") (pintype "passive"))
      (node (ref "Q6") (pin "3") (pinfunction "S_3") (pintype "passive"))
      (node (ref "R11") (pin "2") (pinfunction "2_2") (pintype "passive"))
      (node (ref "R12") (pin "1") (pinfunction "1_1") (pintype "passive"))
      (node (ref "R20") (pin "1") (pinfunction "1_1") (pintype "passive"))
      (node (ref "R21") (pin "1") (pinfunction "1_1") (pintype "passive"))
      (node (ref "R25") (pin "1") (pinfunction "1_1") (pintype "passive"))
      (node (ref "R28") (pin "2") (pinfunction "2_2") (pintype "passive"))
      (node (ref "R31") (pin "1") (pinfunction "1_1") (pintype "passive"))
      (node (ref "R34") (pin "1") (pinfunction "1_1") (pintype "passive"))
      (node (ref "R8") (pin "1") (pinfunction "1_1") (pintype "passive"))
      (node (ref "S1") (pin "1") (pinfunction "1_1") (pintype "passive"))
      (node (ref "S2") (pin "1") (pinfunction "1_1") (pintype "passive"))
      (node (ref "S3") (pin "1") (pinfunction "1_1") (pintype "passive"))
      (node (ref "S4") (pin "1") (pinfunction "1_1") (pintype "passive"))
      (node (ref "SW1") (pin "2") (pinfunction "2_2") (pintype "passive"))
      (node (ref "U1") (pin "18") (pinfunction "VSS_18") (pintype "passive"))
      (node (ref "U1") (pin "70") (pinfunction "VSS_70") (pintype "passive"))
      (node (ref "X1") (pin "2") (pinfunction "GND_2") (pintype "passive"))
      (node (ref "X1") (pin "4") (pinfunction "GND_4") (pintype "passive"))
    )
    (net (code "45") (name "Net-(C10-Pad2)") (class "Default")
      (node (ref "C10") (pin "2") (pinfunction "2_2") (pintype "passive"))
      (node (ref "R1") (pin "1") (pinfunction "1_1") (pintype "passive"))
    )
    (net (code "46") (name "Net-(C11-Pad2)") (class "Default")
      (node (ref "C11") (pin "2") (pinfunction "2_2") (pintype "passive"))
      (node (ref "R2") (pin "1") (pinfunction "1_1") (pintype "passive"))
    )
    (net (code "47") (name "Net-(C12-Pad2)") (class "Default")
      (node (ref "C12") (pin "2") (pinfunction "2_2") (pintype "passive"))
      (node (ref "R3") (pin "1") (pinfunction "1_1") (pintype "passive"))
    )
    (net (code "48") (name "Net-(C17-Pad2)") (class "Default")
      (node (ref "C17") (pin "2") (pinfunction "2_2") (pintype "passive"))
      (node (ref "R16") (pin "1") (pinfunction "1_1") (pintype "passive"))
    )
    (net (code "49") (name "Net-(C18-Pad2)") (class "Default")
      (node (ref "C18") (pin "2") (pinfunction "2_2") (pintype "passive"))
      (node (ref "R17") (pin "1") (pinfunction "1_1") (pintype "passive"))
    )
    (net (code "50") (name "Net-(C19-Pad2)") (class "Default")
      (node (ref "C19") (pin "2") (pinfunction "2_2") (pintype "passive"))
      (node (ref "R18") (pin "1") (pinfunction "1_1") (pintype "passive"))
    )
    (net (code "51") (name "Net-(D1-C)") (class "Default")
      (node (ref "C3") (pin "1") (pinfunction "1_1") (pintype "passive"))
      (node (ref "D1") (pin "1") (pinfunction "C_1") (pintype "passive"))
      (node (ref "IC1") (pin "8") (pinfunction "SW_8") (pintype "passive"))
      (node (ref "L2") (pin "1") (pinfunction "1_1") (pintype "passive"))
    )
    (net (code "52") (name "Net-(Dz1-K)") (class "Default")
      (node (ref "C40") (pin "2") (pinfunction "2_2") (pintype "passive"))
      (node (ref "C41") (pin "2") (pinfunction "2_2") (pintype "passive"))
      (node (ref "Dz1") (pin "1") (pinfunction "K_1") (pintype "passive"))
      (node (ref "IC4") (pin "1") (pinfunction "EN/UVLO_1") (pintype "passive"))
      (node (ref "IC4") (pin "5") (pinfunction "VS_5") (pintype "passive"))
      (node (ref "R26") (pin "1") (pinfunction "1_1") (pintype "passive"))
    )
    (net (code "53") (name "Net-(IC1-BOOT)") (class "Default")
      (node (ref "C3") (pin "2") (pinfunction "2_2") (pintype "passive"))
      (node (ref "IC1") (pin "1") (pinfunction "BOOT_1") (pintype "passive"))
    )
    (net (code "54") (name "Net-(IC1-FB)") (class "Default")
      (node (ref "IC1") (pin "5") (pinfunction "FB_5") (pintype "passive"))
      (node (ref "R11") (pin "1") (pinfunction "1_1") (pintype "passive"))
      (node (ref "R4") (pin "1") (pinfunction "1_1") (pintype "passive"))
    )
    (net (code "55") (name "Net-(IC1-RT{slash}SYNC)") (class "Default")
      (node (ref "IC1") (pin "4") (pinfunction "RT/SYNC_4") (pintype "passive"))
      (node (ref "R8") (pin "2") (pinfunction "2_2") (pintype "passive"))
    )
    (net (code "56") (name "Net-(IC1-SS_or_PGOOD)") (class "Default")
      (node (ref "C9") (pin "2") (pinfunction "2_2") (pintype "passive"))
      (node (ref "IC1") (pin "6") (pinfunction "SS_or_PGOOD_6") (pintype "passive"))
    )
    (net (code "57") (name "Net-(IC2-EN)") (class "Default")
      (node (ref "IC2") (pin "3") (pinfunction "EN_3") (pintype "passive"))
      (node (ref "R19") (pin "1") (pinfunction "1_1") (pintype "passive"))
    )
    (net (code "58") (name "Net-(IC3-AVDD)") (class "Default")
      (node (ref "C31") (pin "1") (pinfunction "1_1") (pintype "passive"))
      (node (ref "IC3") (pin "27") (pinfunction "AVDD_27") (pintype "passive"))
    )
    (net (code "59") (name "Net-(IC3-BST_A)") (class "Default")
      (node (ref "C13") (pin "1") (pinfunction "1_1") (pintype "passive"))
      (node (ref "IC3") (pin "48") (pinfunction "BST_A_48") (pintype "passive"))
    )
    (net (code "60") (name "Net-(IC3-BST_B)") (class "Default")
      (node (ref "C15") (pin "1") (pinfunction "1_1") (pintype "passive"))
      (node (ref "IC3") (pin "43") (pinfunction "BST_B_43") (pintype "passive"))
    )
    (net (code "61") (name "Net-(IC3-BST_C)") (class "Default")
      (node (ref "C20") (pin "1") (pinfunction "1_1") (pintype "passive"))
      (node (ref "IC3") (pin "38") (pinfunction "BST_C_38") (pintype "passive"))
    )
    (net (code "62") (name "Net-(IC3-CP1)") (class "Default")
      (node (ref "C14") (pin "2") (pinfunction "2_2") (pintype "passive"))
      (node (ref "IC3") (pin "14") (pinfunction "CP1_14") (pintype "passive"))
    )
    (net (code "63") (name "Net-(IC3-CP2)") (class "Default")
      (node (ref "C14") (pin "1") (pinfunction "1_1") (pintype "passive"))
      (node (ref "IC3") (pin "15") (pinfunction "CP2_15") (pintype "passive"))
    )
    (net (code "64") (name "Net-(IC3-DTC)") (class "Default")
      (node (ref "IC3") (pin "7") (pinfunction "DTC_7") (pintype "passive"))
      (node (ref "R12") (pin "2") (pinfunction "2_2") (pintype "passive"))
    )
    (net (code "65") (name "Net-(IC3-DVDD)") (class "Default")
      (node (ref "C30") (pin "2") (pinfunction "2_2") (pintype "passive"))
      (node (ref "IC3") (pin "23") (pinfunction "DVDD_23") (pintype "passive"))
    )
    (net (code "66") (name "Net-(IC3-GVDD)") (class "Default")
      (node (ref "C16") (pin "2") (pinfunction "2_2") (pintype "passive"))
      (node (ref "IC3") (pin "13") (pinfunction "GVDD_13") (pintype "passive"))
    )
    (net (code "67") (name "Net-(IC3-SO1)") (class "Default")
      (node (ref "IC3") (pin "25") (pinfunction "SO1_25") (pintype "passive"))
      (node (ref "R22") (pin "1") (pinfunction "1_1") (pintype "passive"))
    )
    (net (code "68") (name "Net-(IC3-SO2)") (class "Default")
      (node (ref "IC3") (pin "26") (pinfunction "SO2_26") (pintype "passive"))
      (node (ref "R23") (pin "1") (pinfunction "1_1") (pintype "passive"))
    )
    (net (code "69") (name "Net-(IC3-nFAULT)") (class "Default")
      (node (ref "IC3") (pin "6") (pinfunction "nFAULT_6") (pintype "passive"))
      (node (ref "R9") (pin "1") (pinfunction "1_1") (pintype "passive"))
    )
    (net (code "70") (name "Net-(IC3-nOCTW)") (class "Default")
      (node (ref "IC3") (pin "5") (pinfunction "nOCTW_5") (pintype "passive"))
      (node (ref "R10") (pin "2") (pinfunction "2_2") (pintype "passive"))
    )
    (net (code "71") (name "Net-(IC4-GATE)") (class "Default")
      (node (ref "IC4") (pin "6") (pinfunction "GATE_6") (pintype "passive"))
      (node (ref "Q7") (pin "4") (pinfunction "G_4") (pintype "passive"))
      (node (ref "Q8") (pin "4") (pinfunction "G_4") (pintype "passive"))
    )
    (net (code "72") (name "Net-(IC4-OV)") (class "Default")
      (node (ref "IC4") (pin "7") (pinfunction "OV_7") (pintype "passive"))
      (node (ref "R24") (pin "1") (pinfunction "1_1") (pintype "passive"))
      (node (ref "R25") (pin "2") (pinfunction "2_2") (pintype "passive"))
    )
    (net (code "73") (name "Net-(IC4-SRC)") (class "Default")
      (node (ref "IC4") (pin "8") (pinfunction "SRC_8") (pintype "passive"))
      (node (ref "Q7") (pin "1") (pinfunction "S_1") (pintype "passive"))
      (node (ref "Q7") (pin "2") (pinfunction "S_2") (pintype "passive"))
      (node (ref "Q7") (pin "3") (pinfunction "S_3") (pintype "passive"))
      (node (ref "Q8") (pin "1") (pinfunction "S_1") (pintype "passive"))
      (node (ref "Q8") (pin "2") (pinfunction "S_2") (pintype "passive"))
      (node (ref "Q8") (pin "3") (pinfunction "S_3") (pintype "passive"))
    )
    (net (code "74") (name "Net-(IC4-VCAP)") (class "Default")
      (node (ref "C40") (pin "1") (pinfunction "1_1") (pintype "passive"))
      (node (ref "IC4") (pin "4") (pinfunction "VCAP_4") (pintype "passive"))
    )
    (net (code "75") (name "Net-(Q1-G)") (class "Default")
      (node (ref "Q1") (pin "4") (pinfunction "G_4") (pintype "passive"))
      (node (ref "R5") (pin "2") (pinfunction "2_2") (pintype "passive"))
    )
    (net (code "76") (name "Net-(Q2-G)") (class "Default")
      (node (ref "Q2") (pin "4") (pinfunction "G_4") (pintype "passive"))
      (node (ref "R7") (pin "2") (pinfunction "2_2") (pintype "passive"))
    )
    (net (code "77") (name "Net-(Q3-G)") (class "Default")
      (node (ref "Q3") (pin "4") (pinfunction "G_4") (pintype "passive"))
      (node (ref "R6") (pin "2") (pinfunction "2_2") (pintype "passive"))
    )
    (net (code "78") (name "Net-(Q4-G)") (class "Default")
      (node (ref "Q4") (pin "4") (pinfunction "G_4") (pintype "passive"))
      (node (ref "R13") (pin "2") (pinfunction "2_2") (pintype "passive"))
    )
    (net (code "79") (name "Net-(Q5-G)") (class "Default")
      (node (ref "Q5") (pin "4") (pinfunction "G_4") (pintype "passive"))
      (node (ref "R14") (pin "2") (pinfunction "2_2") (pintype "passive"))
    )
    (net (code "80") (name "Net-(Q6-G)") (class "Default")
      (node (ref "Q6") (pin "4") (pinfunction "G_4") (pintype "passive"))
      (node (ref "R15") (pin "2") (pinfunction "2_2") (pintype "passive"))
    )
    (net (code "81") (name "Net-(U1A-BOOT0)") (class "Default")
      (node (ref "R31") (pin "2") (pinfunction "2_2") (pintype "passive"))
      (node (ref "U1") (pin "60") (pinfunction "BOOT0_60") (pintype "passive"))
    )
    (net (code "82") (name "Net-(U1A-PB2-BOOT1(PB2))") (class "Default")
      (node (ref "R28") (pin "1") (pinfunction "1_1") (pintype "passive"))
      (node (ref "U1") (pin "28") (pinfunction "PB2-BOOT1(PB2)_28") (pintype "passive"))
    )
    (net (code "83") (name "Net-(U1A-VCAP_1)") (class "Default")
      (node (ref "C55") (pin "2") (pinfunction "2_2") (pintype "passive"))
      (node (ref "U1") (pin "31") (pinfunction "VCAP_1_31") (pintype "passive"))
    )
    (net (code "84") (name "Net-(U1A-VCAP_2)") (class "Default")
      (node (ref "C56") (pin "2") (pinfunction "2_2") (pintype "passive"))
      (node (ref "U1") (pin "47") (pinfunction "VCAP_2_47") (pintype "passive"))
    )
    (net (code "85") (name "POWER_BUCK") (class "Default")
      (node (ref "C4") (pin "1") (pinfunction "1_1") (pintype "passive"))
      (node (ref "IC1") (pin "2") (pinfunction "VIN_2") (pintype "passive"))
      (node (ref "IC1") (pin "3") (pinfunction "EN_3") (pintype "passive"))
      (node (ref "L1") (pin "2") (pinfunction "2_2") (pintype "passive"))
    )
    (net (code "86") (name "POWER_IN") (class "Default")
      (node (ref "C21") (pin "2") (pinfunction "2_2") (pintype "passive"))
      (node (ref "D2") (pin "2") (pinfunction "2_2") (pintype "passive"))
      (node (ref "J1") (pin "1") (pintype "passive"))
      (node (ref "Q7") (pin "5") (pinfunction "D_5") (pintype "passive"))
      (node (ref "Q7") (pin "6") (pinfunction "D_6") (pintype "passive"))
      (node (ref "Q7") (pin "7") (pinfunction "D_7") (pintype "passive"))
      (node (ref "Q7") (pin "8") (pinfunction "D_8") (pintype "passive"))
      (node (ref "Q7") (pin "9") (pinfunction "D_9") (pintype "passive"))
      (node (ref "R24") (pin "2") (pinfunction "2_2") (pintype "passive"))
      (node (ref "R26") (pin "2") (pinfunction "2_2") (pintype "passive"))
    )
    (net (code "87") (name "POWER_LOAD") (class "Default")
      (node (ref "C34") (pin "2") (pinfunction "2_2") (pintype "passive"))
      (node (ref "C35") (pin "2") (pinfunction "2_2") (pintype "passive"))
      (node (ref "C36") (pin "1") (pinfunction "1_1") (pintype "passive"))
      (node (ref "C37") (pin "1") (pinfunction "1_1") (pintype "passive"))
      (node (ref "C38") (pin "1") (pinfunction "1_1") (pintype "passive"))
      (node (ref "C39") (pin "1") (pinfunction "1_1") (pintype "passive"))
      (node (ref "C5") (pin "2") (pinfunction "2_2") (pintype "passive"))
      (node (ref "C8") (pin "1") (pinfunction "1_1") (pintype "passive"))
      (node (ref "IC3") (pin "29") (pinfunction "PVDD1_29") (pintype "passive"))
      (node (ref "L1") (pin "1") (pinfunction "1_1") (pintype "passive"))
      (node (ref "Q1") (pin "5") (pinfunction "D_5") (pintype "passive"))
      (node (ref "Q1") (pin "6") (pinfunction "D_6") (pintype "passive"))
      (node (ref "Q1") (pin "7") (pinfunction "D_7") (pintype "passive"))
      (node (ref "Q1") (pin "8") (pinfunction "D_8") (pintype "passive"))
      (node (ref "Q1") (pin "9") (pinfunction "D_9") (pintype "passive"))
      (node (ref "Q2") (pin "5") (pinfunction "D_5") (pintype "passive"))
      (node (ref "Q2") (pin "6") (pinfunction "D_6") (pintype "passive"))
      (node (ref "Q2") (pin "7") (pinfunction "D_7") (pintype "passive"))
      (node (ref "Q2") (pin "8") (pinfunction "D_8") (pintype "passive"))
      (node (ref "Q2") (pin "9") (pinfunction "D_9") (pintype "passive"))
      (node (ref "Q3") (pin "5") (pinfunction "D_5") (pintype "passive"))
      (node (ref "Q3") (pin "6") (pinfunction "D_6") (pintype "passive"))
      (node (ref "Q3") (pin "7") (pinfunction "D_7") (pintype "passive"))
      (node (ref "Q3") (pin "8") (pinfunction "D_8") (pintype "passive"))
      (node (ref "Q3") (pin "9") (pinfunction "D_9") (pintype "passive"))
      (node (ref "Q8") (pin "5") (pinfunction "D_5") (pintype "passive"))
      (node (ref "Q8") (pin "6") (pinfunction "D_6") (pintype "passive"))
      (node (ref "Q8") (pin "7") (pinfunction "D_7") (pintype "passive"))
      (node (ref "Q8") (pin "8") (pinfunction "D_8") (pintype "passive"))
      (node (ref "Q8") (pin "9") (pinfunction "D_9") (pintype "passive"))
      (node (ref "R1") (pin "2") (pinfunction "2_2") (pintype "passive"))
      (node (ref "R2") (pin "2") (pinfunction "2_2") (pintype "passive"))
      (node (ref "R3") (pin "2") (pinfunction "2_2") (pintype "passive"))
    )
    (net (code "88") (name "V_5V") (class "Default")
      (node (ref "C22") (pin "2") (pinfunction "2_2") (pintype "passive"))
      (node (ref "C48") (pin "2") (pinfunction "2_2") (pintype "passive"))
      (node (ref "C49") (pin "2") (pinfunction "2_2") (pintype "passive"))
      (node (ref "C6") (pin "2") (pinfunction "2_2") (pintype "passive"))
      (node (ref "C7") (pin "2") (pinfunction "2_2") (pintype "passive"))
      (node (ref "IC2") (pin "1") (pinfunction "VIN_1") (pintype "passive"))
      (node (ref "IC5") (pin "3") (pinfunction "VCC_3") (pintype "passive"))
      (node (ref "L2") (pin "2") (pinfunction "2_2") (pintype "passive"))
      (node (ref "R19") (pin "2") (pinfunction "2_2") (pintype "passive"))
      (node (ref "R4") (pin "2") (pinfunction "2_2") (pintype "passive"))
    )
    (net (code "89") (name "unconnected-(IC2-NC-Pad4)") (class "Default")
      (node (ref "IC2") (pin "4") (pinfunction "NC_4") (pintype "passive+no_connect"))
    )
    (net (code "90") (name "unconnected-(IC3-BST_BK-Pad52)") (class "Default")
      (node (ref "IC3") (pin "52") (pinfunction "BST_BK_52") (pintype "passive+no_connect"))
    )
    (net (code "91") (name "unconnected-(IC3-COMP-Pad2)") (class "Default")
      (node (ref "IC3") (pin "2") (pinfunction "COMP_2") (pintype "passive+no_connect"))
    )
    (net (code "92") (name "unconnected-(IC3-PH-Pad50)") (class "Default")
      (node (ref "IC3") (pin "50") (pinfunction "PH_50") (pintype "passive+no_connect"))
    )
    (net (code "93") (name "unconnected-(IC3-PH-Pad51)") (class "Default")
      (node (ref "IC3") (pin "51") (pinfunction "PH_51") (pintype "passive+no_connect"))
    )
    (net (code "94") (name "unconnected-(IC3-PVDD2-Pad53)") (class "Default")
      (node (ref "IC3") (pin "53") (pinfunction "PVDD2_53") (pintype "passive+no_connect"))
    )
    (net (code "95") (name "unconnected-(IC3-PVDD2-Pad54)") (class "Default")
      (node (ref "IC3") (pin "54") (pinfunction "PVDD2_54") (pintype "passive+no_connect"))
    )
    (net (code "96") (name "unconnected-(IC3-PWRGD-Pad4)") (class "Default")
      (node (ref "IC3") (pin "4") (pinfunction "PWRGD_4") (pintype "passive+no_connect"))
    )
    (net (code "97") (name "unconnected-(IC3-RT_CLK-Pad1)") (class "Default")
      (node (ref "IC3") (pin "1") (pinfunction "RT_CLK_1") (pintype "passive+no_connect"))
    )
    (net (code "98") (name "unconnected-(IC3-SS_TR-Pad56)") (class "Default")
      (node (ref "IC3") (pin "56") (pinfunction "SS_TR_56") (pintype "passive+no_connect"))
    )
    (net (code "99") (name "unconnected-(IC3-VSENSE-Pad3)") (class "Default")
      (node (ref "IC3") (pin "3") (pinfunction "VSENSE_3") (pintype "passive+no_connect"))
    )
    (net (code "100") (name "unconnected-(IC4-N.C-Pad3)") (class "Default")
      (node (ref "IC4") (pin "3") (pinfunction "N.C_3") (pintype "passive+no_connect"))
    )
    (net (code "101") (name "unconnected-(U1A-PA2-Pad16)") (class "Default")
      (node (ref "U1") (pin "16") (pinfunction "PA2_16") (pintype "passive+no_connect"))
    )
    (net (code "102") (name "unconnected-(U1A-PA3-Pad17)") (class "Default")
      (node (ref "U1") (pin "17") (pinfunction "PA3_17") (pintype "passive+no_connect"))
    )
    (net (code "103") (name "unconnected-(U1A-PA5-Pad21)") (class "Default")
      (node (ref "U1") (pin "21") (pinfunction "PA5_21") (pintype "passive+no_connect"))
    )
    (net (code "104") (name "unconnected-(U1A-PA7-Pad23)") (class "Default")
      (node (ref "U1") (pin "23") (pinfunction "PA7_23") (pintype "passive+no_connect"))
    )
    (net (code "105") (name "unconnected-(U1A-PA11-Pad44)") (class "Default")
      (node (ref "U1") (pin "44") (pinfunction "PA11_44") (pintype "passive+no_connect"))
    )
    (net (code "106") (name "unconnected-(U1A-PA12-Pad45)") (class "Default")
      (node (ref "U1") (pin "45") (pinfunction "PA12_45") (pintype "passive+no_connect"))
    )
    (net (code "107") (name "unconnected-(U1A-PA15(JTDI)-Pad50)") (class "Default")
      (node (ref "U1") (pin "50") (pinfunction "PA15(JTDI)_50") (pintype "passive+no_connect"))
    )
    (net (code "108") (name "unconnected-(U1A-PB0-Pad26)") (class "Default")
      (node (ref "U1") (pin "26") (pinfunction "PB0_26") (pintype "passive+no_connect"))
    )
    (net (code "109") (name "unconnected-(U1A-PB1-Pad27)") (class "Default")
      (node (ref "U1") (pin "27") (pinfunction "PB1_27") (pintype "passive+no_connect"))
    )
    (net (code "110") (name "unconnected-(U1A-PB3(JTDOTRACESWO)-Pad55)") (class "Default")
      (node (ref "U1") (pin "55") (pinfunction "PB3(JTDOTRACESWO)_55") (pintype "passive+no_connect"))
    )
    (net (code "111") (name "unconnected-(U1A-PB4(NJTRST)-Pad56)") (class "Default")
      (node (ref "U1") (pin "56") (pinfunction "PB4(NJTRST)_56") (pintype "passive+no_connect"))
    )
    (net (code "112") (name "unconnected-(U1A-PB5-Pad57)") (class "Default")
      (node (ref "U1") (pin "57") (pinfunction "PB5_57") (pintype "passive+no_connect"))
    )
    (net (code "113") (name "unconnected-(U1A-PB6-Pad58)") (class "Default")
      (node (ref "U1") (pin "58") (pinfunction "PB6_58") (pintype "passive+no_connect"))
    )
    (net (code "114") (name "unconnected-(U1A-PB7-Pad59)") (class "Default")
      (node (ref "U1") (pin "59") (pinfunction "PB7_59") (pintype "passive+no_connect"))
    )
    (net (code "115") (name "unconnected-(U1A-PB10-Pad29)") (class "Default")
      (node (ref "U1") (pin "29") (pinfunction "PB10_29") (pintype "passive+no_connect"))
    )
    (net (code "116") (name "unconnected-(U1A-PB11-Pad30)") (class "Default")
      (node (ref "U1") (pin "30") (pinfunction "PB11_30") (pintype "passive+no_connect"))
    )
    (net (code "117") (name "unconnected-(U1A-PB12-Pad33)") (class "Default")
      (node (ref "U1") (pin "33") (pinfunction "PB12_33") (pintype "passive+no_connect"))
    )
    (net (code "118") (name "unconnected-(U1A-PC0-Pad8)") (class "Default")
      (node (ref "U1") (pin "8") (pinfunction "PC0_8") (pintype "passive+no_connect"))
    )
    (net (code "119") (name "unconnected-(U1A-PC1-Pad9)") (class "Default")
      (node (ref "U1") (pin "9") (pinfunction "PC1_9") (pintype "passive+no_connect"))
    )
    (net (code "120") (name "unconnected-(U1A-PC4-Pad24)") (class "Default")
      (node (ref "U1") (pin "24") (pinfunction "PC4_24") (pintype "passive+no_connect"))
    )
    (net (code "121") (name "unconnected-(U1A-PC5-Pad25)") (class "Default")
      (node (ref "U1") (pin "25") (pinfunction "PC5_25") (pintype "passive+no_connect"))
    )
    (net (code "122") (name "unconnected-(U1A-PC6-Pad37)") (class "Default")
      (node (ref "U1") (pin "37") (pinfunction "PC6_37") (pintype "passive+no_connect"))
    )
    (net (code "123") (name "unconnected-(U1A-PC7-Pad38)") (class "Default")
      (node (ref "U1") (pin "38") (pinfunction "PC7_38") (pintype "passive+no_connect"))
    )
    (net (code "124") (name "unconnected-(U1A-PC8-Pad39)") (class "Default")
      (node (ref "U1") (pin "39") (pinfunction "PC8_39") (pintype "passive+no_connect"))
    )
    (net (code "125") (name "unconnected-(U1A-PC9-Pad40)") (class "Default")
      (node (ref "U1") (pin "40") (pinfunction "PC9_40") (pintype "passive+no_connect"))
    )
    (net (code "126") (name "unconnected-(U1A-PC13-Pad2)") (class "Default")
      (node (ref "U1") (pin "2") (pinfunction "PC13_2") (pintype "passive+no_connect"))
    )
    (net (code "127") (name "unconnected-(U1A-PC14-OSC32_IN(PC14)-Pad3)") (class "Default")
      (node (ref "U1") (pin "3") (pinfunction "PC14-OSC32_IN(PC14)_3") (pintype "passive+no_connect"))
    )
    (net (code "128") (name "unconnected-(U1A-PC15-OSC32_OUT(PC15)-Pad4)") (class "Default")
      (node (ref "U1") (pin "4") (pinfunction "PC15-OSC32_OUT(PC15)_4") (pintype "passive+no_connect"))
    )
    (net (code "129") (name "unconnected-(U1A-PD2-Pad54)") (class "Default")
      (node (ref "U1") (pin "54") (pinfunction "PD2_54") (pintype "passive+no_connect"))
    )
  )
)
